# oresat-c3-v1.net
KiCad netlist of a schematic drawn in EAGLE
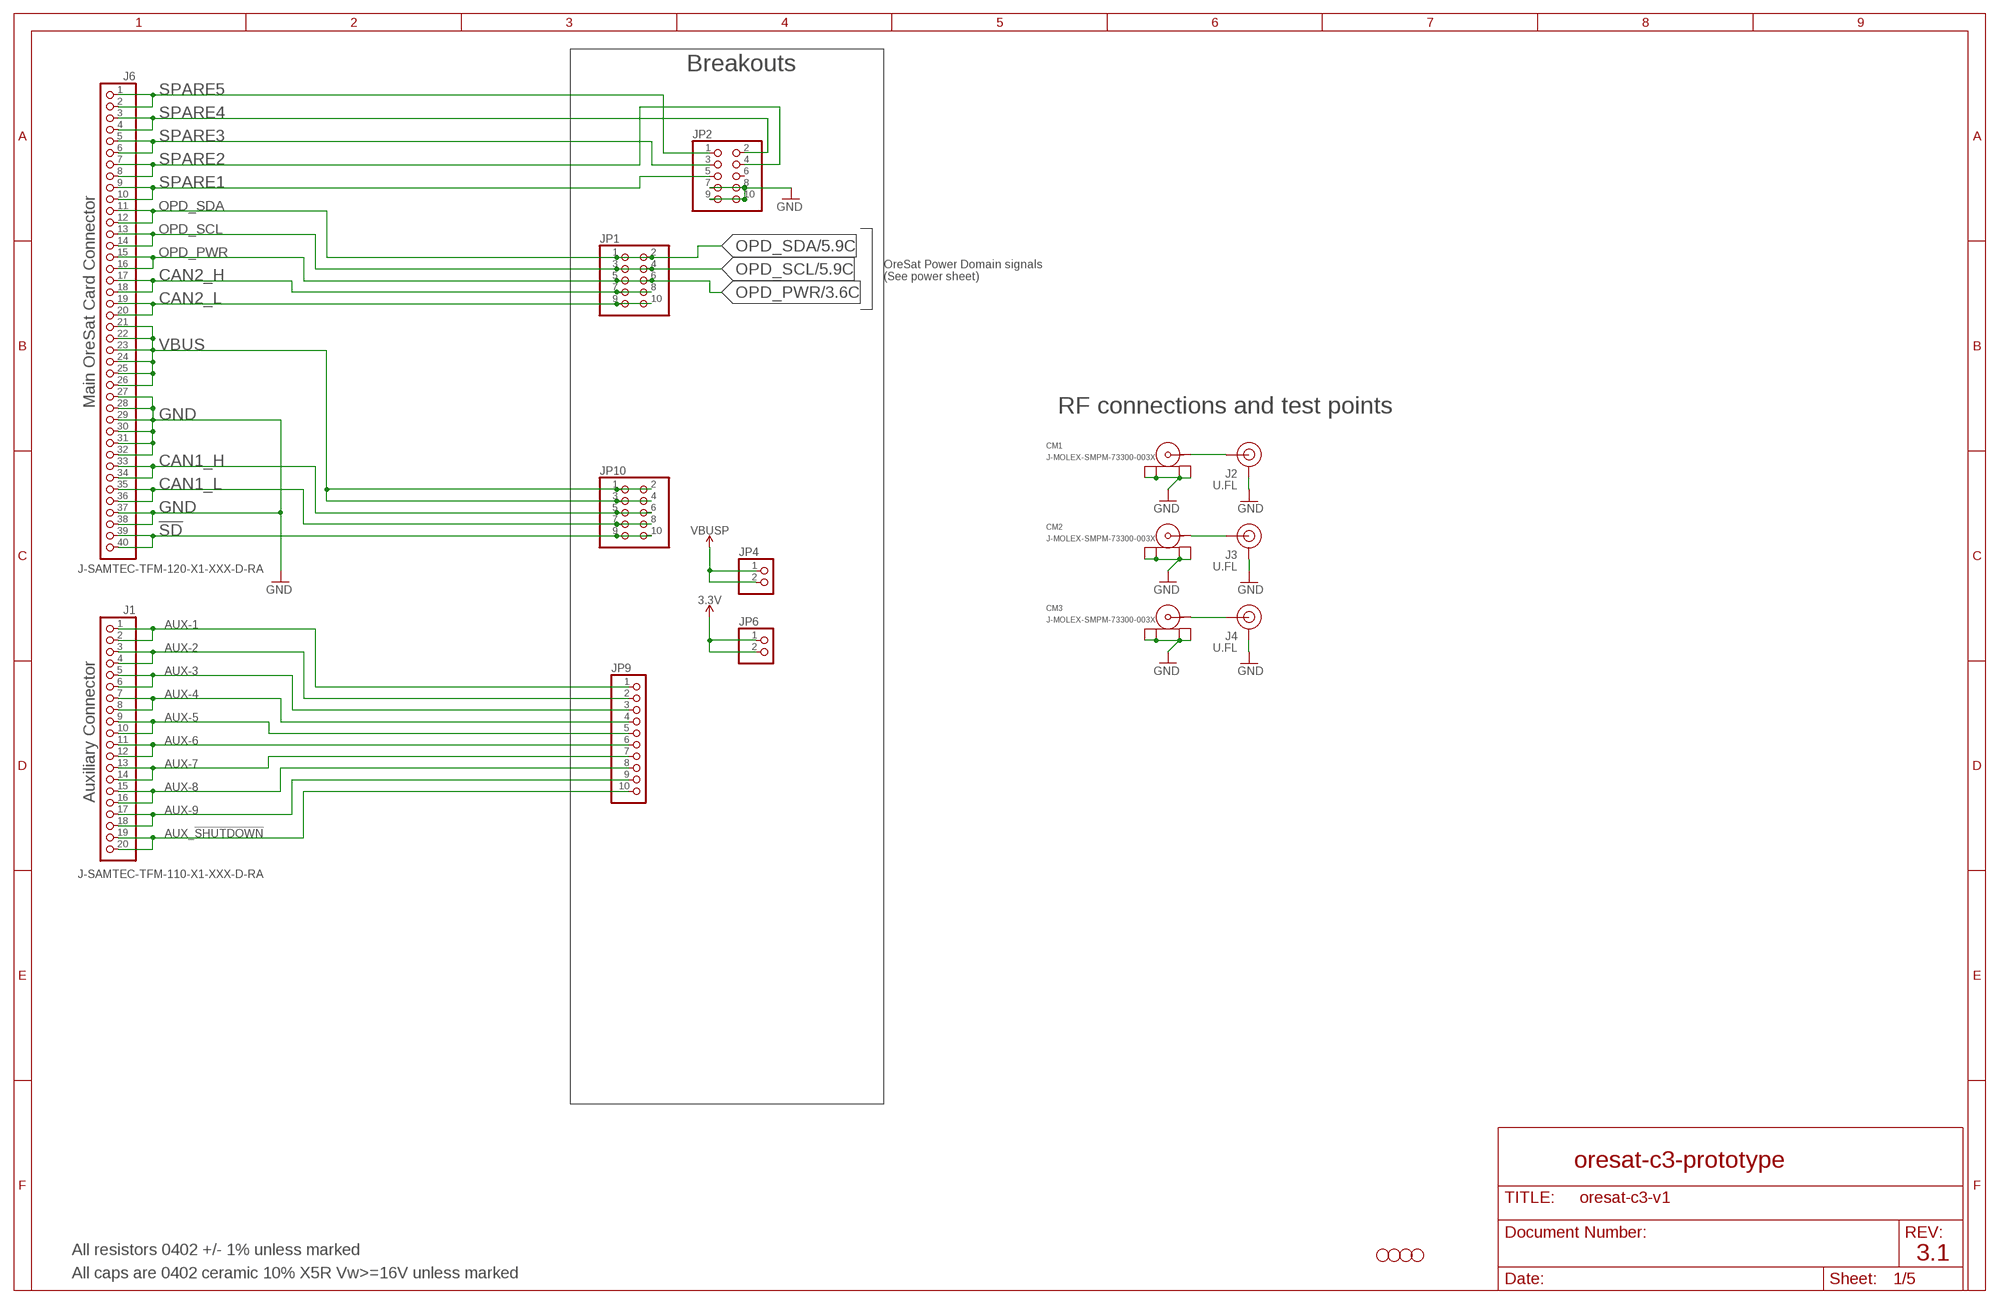
[diagram p0: schematic, sheet 1]
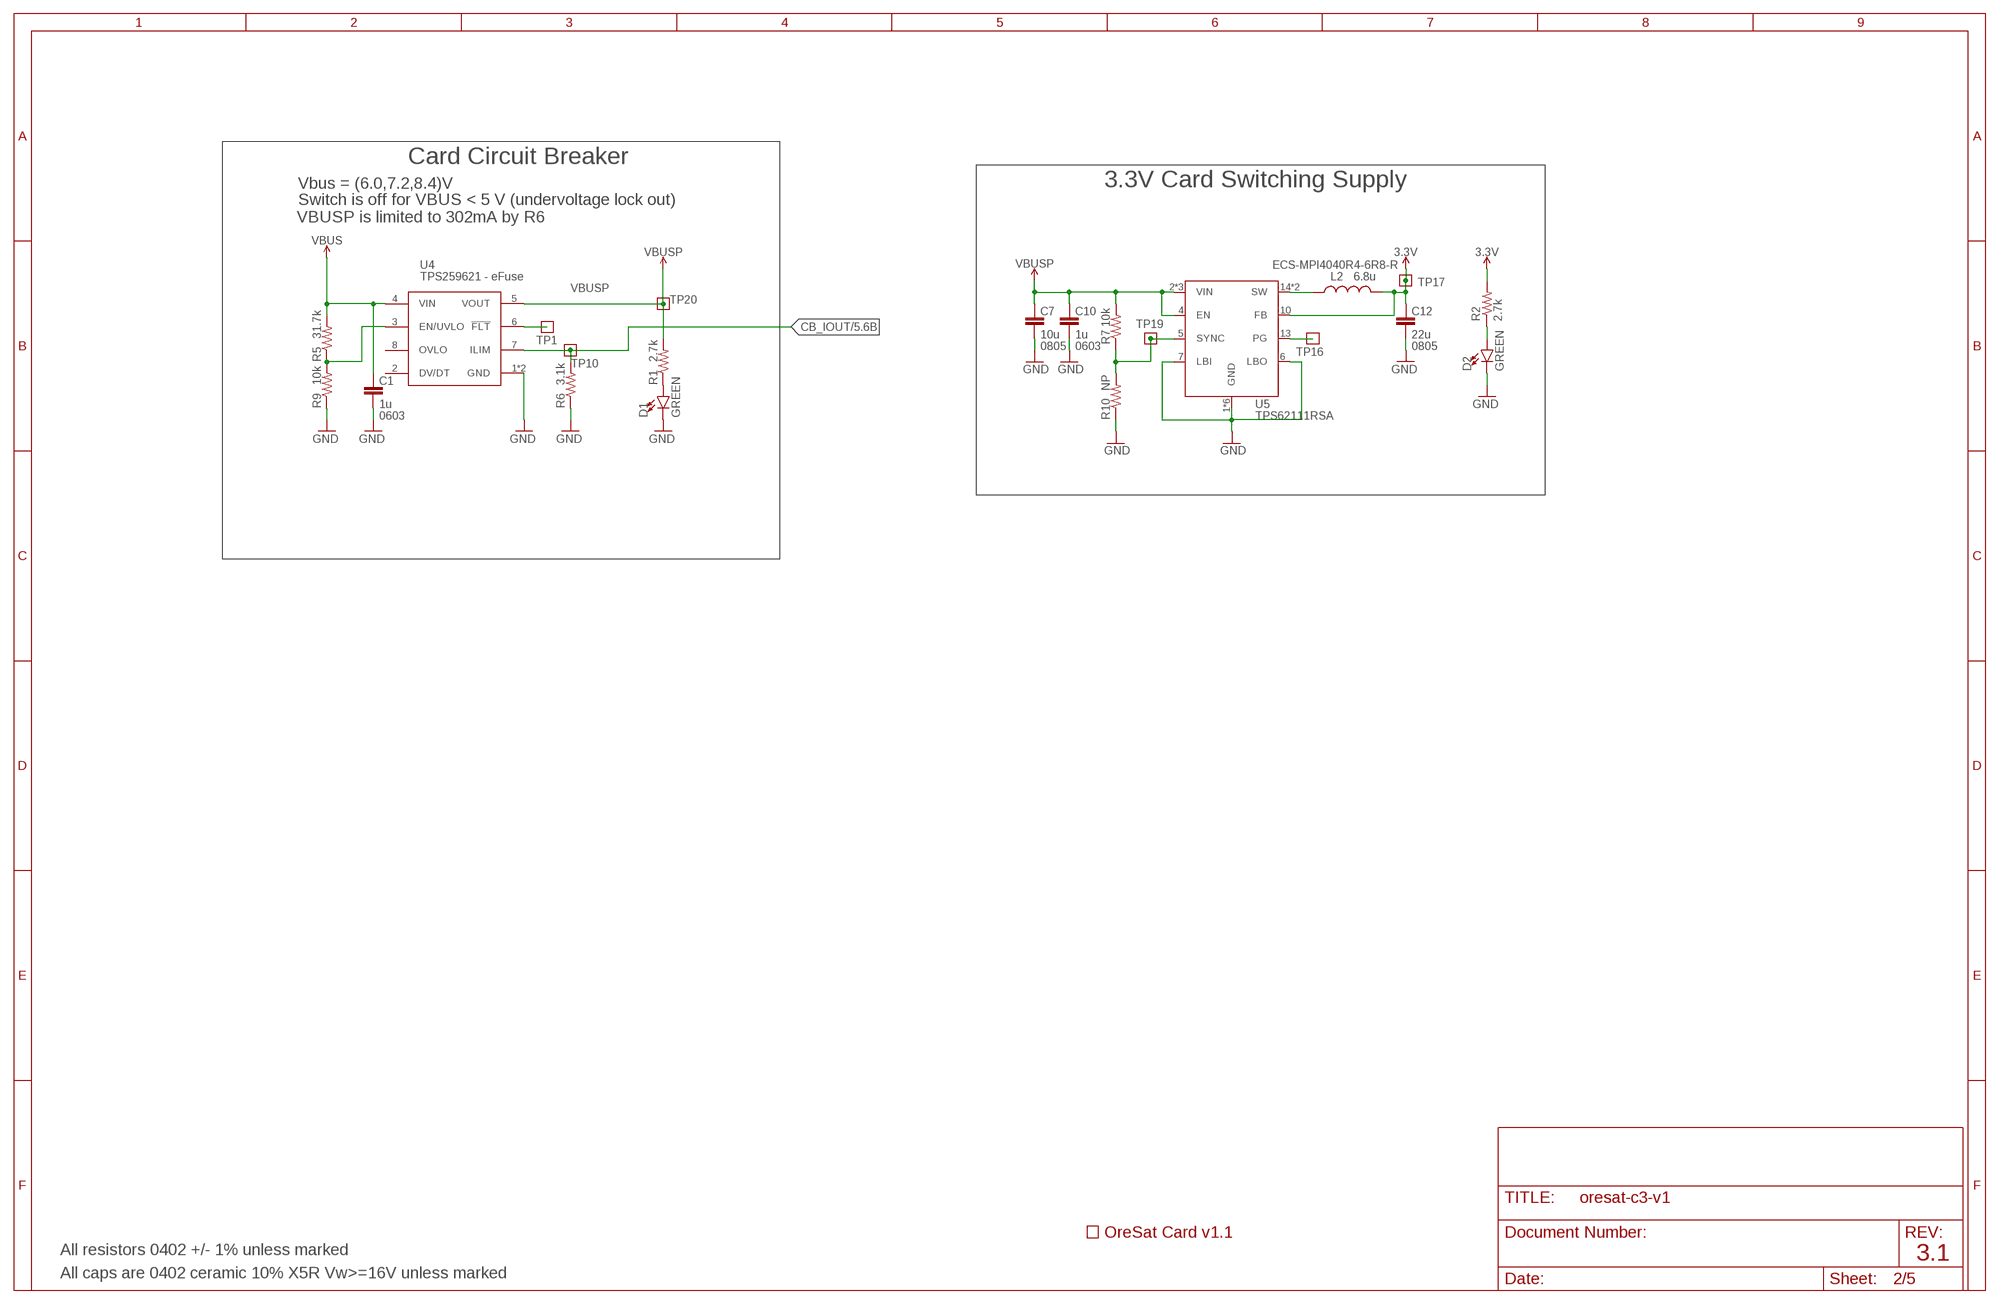
[diagram p1: schematic, sheet 2]
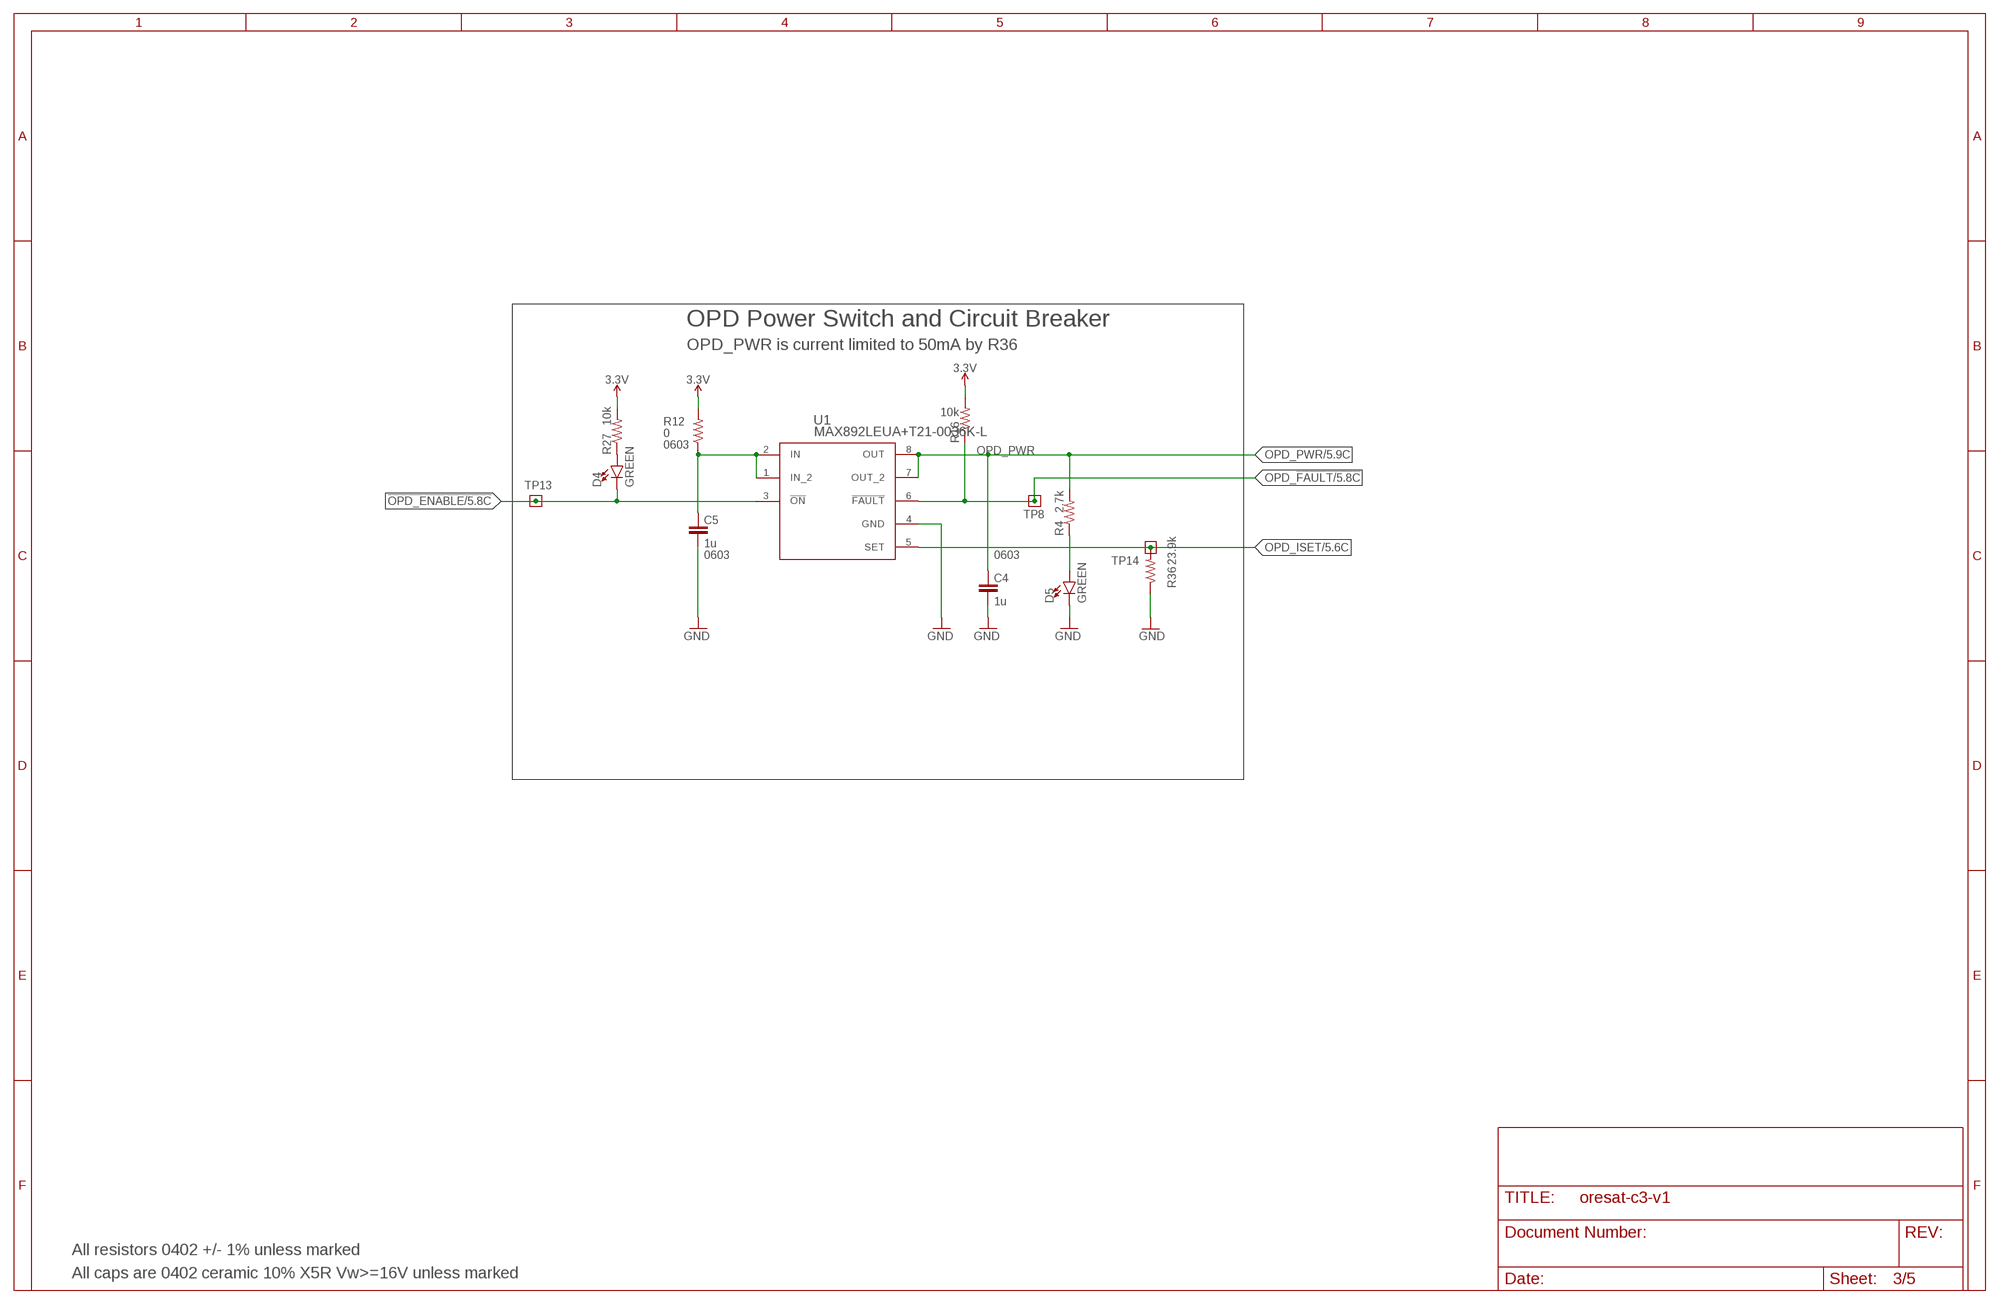
[diagram p2: schematic, sheet 3]
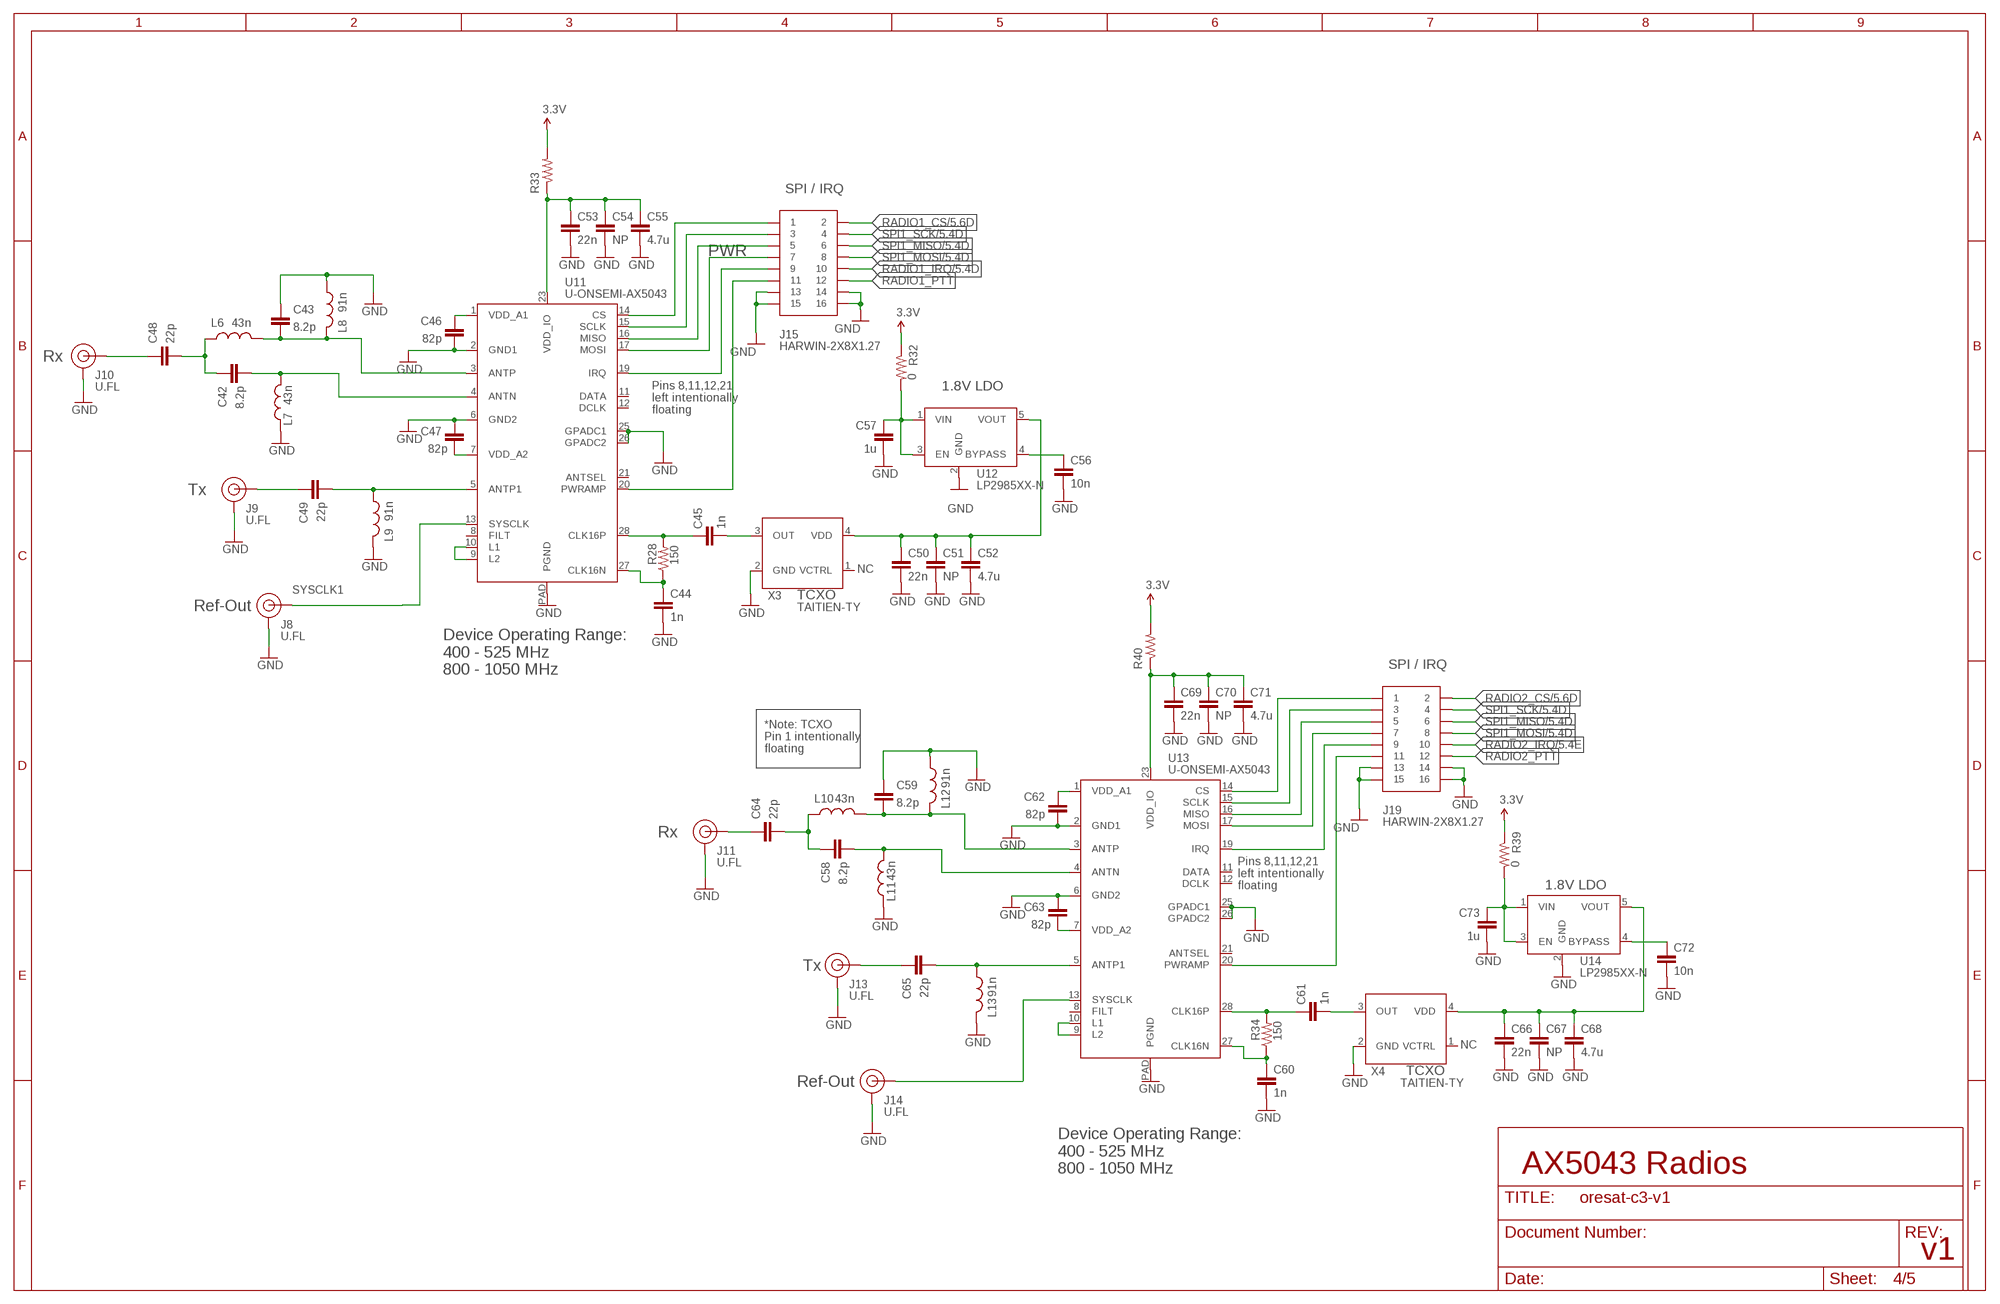
[diagram p3: schematic, sheet 4]
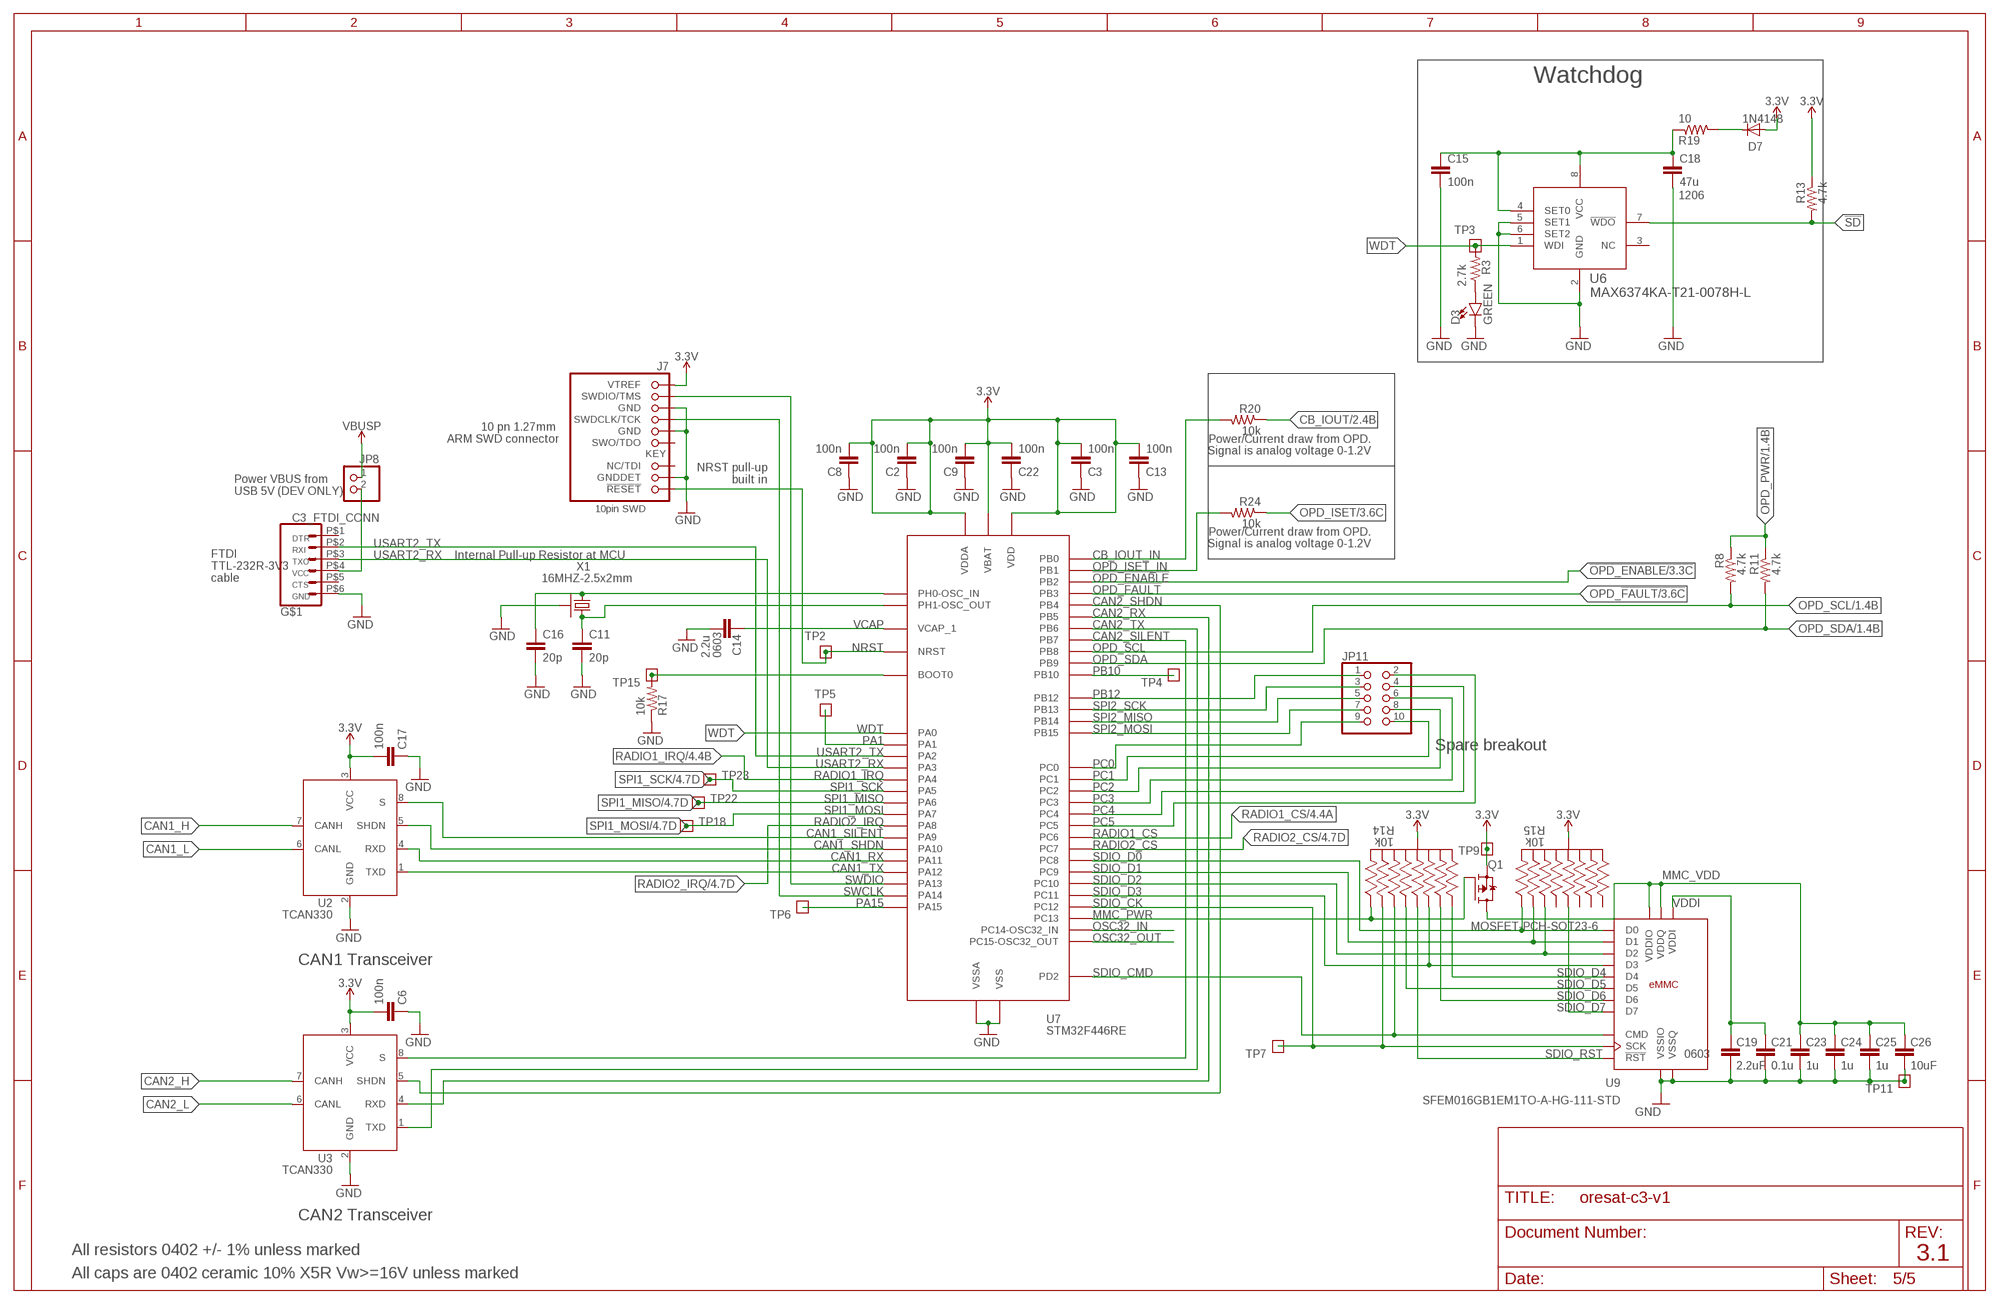
[diagram p4: schematic, sheet 5]

(export (version "E")
  (design (tool "Eeschema 10.0.6"))
  (components
    (comp (ref "C42")
      (value "8.2p")
      (footprint "eagle-import:.0402-C-NOSILK")
      (libsource (lib "eagle-import") (part "C-EU0402-C-NOSILK"))
    )
    (comp (ref "C43")
      (value "8.2p")
      (footprint "eagle-import:.0402-C-NOSILK")
      (libsource (lib "eagle-import") (part "C-EU0402-C-NOSILK"))
    )
    (comp (ref "C44")
      (value "1n")
      (footprint "eagle-import:.0402-C-NOSILK")
      (libsource (lib "eagle-import") (part "C-EU0402-C-NOSILK"))
    )
    (comp (ref "C45")
      (value "1n")
      (footprint "eagle-import:.0402-C-NOSILK")
      (libsource (lib "eagle-import") (part "C-EU0402-C-NOSILK"))
    )
    (comp (ref "C46")
      (value "82p")
      (footprint "eagle-import:.0402-C-NOSILK")
      (libsource (lib "eagle-import") (part "C-EU0402-C-NOSILK"))
    )
    (comp (ref "C47")
      (value "82p")
      (footprint "eagle-import:.0402-C-NOSILK")
      (libsource (lib "eagle-import") (part "C-EU0402-C-NOSILK"))
    )
    (comp (ref "C48")
      (value "22p")
      (footprint "eagle-import:.0402-C-NOSILK")
      (libsource (lib "eagle-import") (part "C-EU0402-C-NOSILK"))
    )
    (comp (ref "C49")
      (value "22p")
      (footprint "eagle-import:.0402-C-NOSILK")
      (libsource (lib "eagle-import") (part "C-EU0402-C-NOSILK"))
    )
    (comp (ref "C50")
      (value "22n")
      (footprint "eagle-import:.0603-C-NOSILK")
      (libsource (lib "eagle-import") (part "C-EU0603-C-NOSILK"))
    )
    (comp (ref "C51")
      (value "NP")
      (footprint "eagle-import:.0603-C-NOSILK")
      (libsource (lib "eagle-import") (part "C-EU0603-C-NOSILK"))
    )
    (comp (ref "C52")
      (value "4.7u")
      (footprint "eagle-import:.0603-C-NOSILK")
      (libsource (lib "eagle-import") (part "C-EU0603-C-NOSILK"))
    )
    (comp (ref "C53")
      (value "22n")
      (footprint "eagle-import:.0603-C-NOSILK")
      (libsource (lib "eagle-import") (part "C-EU0603-C-NOSILK"))
    )
    (comp (ref "C54")
      (value "NP")
      (footprint "eagle-import:.0603-C-NOSILK")
      (libsource (lib "eagle-import") (part "C-EU0603-C-NOSILK"))
    )
    (comp (ref "C55")
      (value "4.7u")
      (footprint "eagle-import:.0603-C-NOSILK")
      (libsource (lib "eagle-import") (part "C-EU0603-C-NOSILK"))
    )
    (comp (ref "C56")
      (value "10n")
      (footprint "eagle-import:.0603-C-NOSILK")
      (libsource (lib "eagle-import") (part "C-EU0603-C-NOSILK"))
    )
    (comp (ref "C57")
      (value "1u")
      (footprint "eagle-import:.0603-C-NOSILK")
      (libsource (lib "eagle-import") (part "C-EU0603-C-NOSILK"))
    )
    (comp (ref "C58")
      (value "8.2p")
      (footprint "eagle-import:.0402-C-NOSILK")
      (libsource (lib "eagle-import") (part "C-EU0402-C-NOSILK"))
    )
    (comp (ref "C59")
      (value "8.2p")
      (footprint "eagle-import:.0402-C-NOSILK")
      (libsource (lib "eagle-import") (part "C-EU0402-C-NOSILK"))
    )
    (comp (ref "C60")
      (value "1n")
      (footprint "eagle-import:.0402-C-NOSILK")
      (libsource (lib "eagle-import") (part "C-EU0402-C-NOSILK"))
    )
    (comp (ref "C61")
      (value "1n")
      (footprint "eagle-import:.0402-C-NOSILK")
      (libsource (lib "eagle-import") (part "C-EU0402-C-NOSILK"))
    )
    (comp (ref "C62")
      (value "82p")
      (footprint "eagle-import:.0402-C-NOSILK")
      (libsource (lib "eagle-import") (part "C-EU0402-C-NOSILK"))
    )
    (comp (ref "C63")
      (value "82p")
      (footprint "eagle-import:.0402-C-NOSILK")
      (libsource (lib "eagle-import") (part "C-EU0402-C-NOSILK"))
    )
    (comp (ref "C64")
      (value "22p")
      (footprint "eagle-import:.0402-C-NOSILK")
      (libsource (lib "eagle-import") (part "C-EU0402-C-NOSILK"))
    )
    (comp (ref "C65")
      (value "22p")
      (footprint "eagle-import:.0402-C-NOSILK")
      (libsource (lib "eagle-import") (part "C-EU0402-C-NOSILK"))
    )
    (comp (ref "C66")
      (value "22n")
      (footprint "eagle-import:.0603-C-NOSILK")
      (libsource (lib "eagle-import") (part "C-EU0603-C-NOSILK"))
    )
    (comp (ref "C67")
      (value "NP")
      (footprint "eagle-import:.0603-C-NOSILK")
      (libsource (lib "eagle-import") (part "C-EU0603-C-NOSILK"))
    )
    (comp (ref "C68")
      (value "4.7u")
      (footprint "eagle-import:.0603-C-NOSILK")
      (libsource (lib "eagle-import") (part "C-EU0603-C-NOSILK"))
    )
    (comp (ref "C69")
      (value "22n")
      (footprint "eagle-import:.0603-C-NOSILK")
      (libsource (lib "eagle-import") (part "C-EU0603-C-NOSILK"))
    )
    (comp (ref "C70")
      (value "NP")
      (footprint "eagle-import:.0603-C-NOSILK")
      (libsource (lib "eagle-import") (part "C-EU0603-C-NOSILK"))
    )
    (comp (ref "C71")
      (value "4.7u")
      (footprint "eagle-import:.0603-C-NOSILK")
      (libsource (lib "eagle-import") (part "C-EU0603-C-NOSILK"))
    )
    (comp (ref "C72")
      (value "10n")
      (footprint "eagle-import:.0603-C-NOSILK")
      (libsource (lib "eagle-import") (part "C-EU0603-C-NOSILK"))
    )
    (comp (ref "C73")
      (value "1u")
      (footprint "eagle-import:.0603-C-NOSILK")
      (libsource (lib "eagle-import") (part "C-EU0603-C-NOSILK"))
    )
    (comp (ref "J8")
      (value "U.FL")
      (footprint "eagle-import:U.FL")
      (libsource (lib "eagle-import") (part "U.FL2PIN"))
    )
    (comp (ref "J9")
      (value "U.FL")
      (footprint "eagle-import:U.FL")
      (libsource (lib "eagle-import") (part "U.FL2PIN"))
    )
    (comp (ref "J10")
      (value "U.FL")
      (footprint "eagle-import:U.FL")
      (libsource (lib "eagle-import") (part "U.FL2PIN"))
    )
    (comp (ref "J11")
      (value "U.FL")
      (footprint "eagle-import:U.FL")
      (libsource (lib "eagle-import") (part "U.FL2PIN"))
    )
    (comp (ref "J13")
      (value "U.FL")
      (footprint "eagle-import:U.FL")
      (libsource (lib "eagle-import") (part "U.FL2PIN"))
    )
    (comp (ref "J14")
      (value "U.FL")
      (footprint "eagle-import:U.FL")
      (libsource (lib "eagle-import") (part "U.FL2PIN"))
    )
    (comp (ref "J15")
      (value "HARWIN-2X8X1.27")
      (footprint "eagle-import:2X8X1.27")
      (libsource (lib "eagle-import") (part "HARWIN-2X8X1.27"))
    )
    (comp (ref "J19")
      (value "HARWIN-2X8X1.27")
      (footprint "eagle-import:2X8X1.27")
      (libsource (lib "eagle-import") (part "HARWIN-2X8X1.27"))
    )
    (comp (ref "L6")
      (value "43n")
      (footprint "eagle-import:.0402-C-NOSILK")
      (libsource (lib "eagle-import") (part "L-US0402-C-NOSILK"))
    )
    (comp (ref "L7")
      (value "43n")
      (footprint "eagle-import:.0402-C-NOSILK")
      (libsource (lib "eagle-import") (part "L-US0402-C-NOSILK"))
    )
    (comp (ref "L8")
      (value "91n")
      (footprint "eagle-import:.0603-C-NOSILK")
      (libsource (lib "eagle-import") (part "L-US0603-C-NOSILK"))
    )
    (comp (ref "L9")
      (value "91n")
      (footprint "eagle-import:.0603-C-NOSILK")
      (libsource (lib "eagle-import") (part "L-US0603-C-NOSILK"))
    )
    (comp (ref "L10")
      (value "43n")
      (footprint "eagle-import:.0402-C-NOSILK")
      (libsource (lib "eagle-import") (part "L-US0402-C-NOSILK"))
    )
    (comp (ref "L11")
      (value "43n")
      (footprint "eagle-import:.0402-C-NOSILK")
      (libsource (lib "eagle-import") (part "L-US0402-C-NOSILK"))
    )
    (comp (ref "L12")
      (value "91n")
      (footprint "eagle-import:.0603-C-NOSILK")
      (libsource (lib "eagle-import") (part "L-US0603-C-NOSILK"))
    )
    (comp (ref "L13")
      (value "91n")
      (footprint "eagle-import:.0603-C-NOSILK")
      (libsource (lib "eagle-import") (part "L-US0603-C-NOSILK"))
    )
    (comp (ref "R28")
      (value "150")
      (footprint "eagle-import:.0402-C-NOSILK")
      (libsource (lib "eagle-import") (part "R-US_0402-C-NOSILK"))
    )
    (comp (ref "R32")
      (value "0")
      (footprint "eagle-import:.0603-C-NOSILK")
      (libsource (lib "eagle-import") (part "R-US_0603-C-NOSILK"))
    )
    (comp (ref "R33")
      (value "0")
      (footprint "eagle-import:.0603-C-NOSILK")
      (libsource (lib "eagle-import") (part "R-US_0603-C-NOSILK"))
    )
    (comp (ref "R34")
      (value "150")
      (footprint "eagle-import:.0402-C-NOSILK")
      (libsource (lib "eagle-import") (part "R-US_0402-C-NOSILK"))
    )
    (comp (ref "R39")
      (value "0")
      (footprint "eagle-import:.0603-C-NOSILK")
      (libsource (lib "eagle-import") (part "R-US_0603-C-NOSILK"))
    )
    (comp (ref "R40")
      (value "0")
      (footprint "eagle-import:.0603-C-NOSILK")
      (libsource (lib "eagle-import") (part "R-US_0603-C-NOSILK"))
    )
    (comp (ref "U11")
      (value "U-ONSEMI-AX5043")
      (footprint "eagle-import:QFN28-5X5-WITH-CENTER-PAD")
      (libsource (lib "eagle-import") (part "U-ONSEMI-AX5043"))
    )
    (comp (ref "U12")
      (value "LP2985XX-N")
      (footprint "eagle-import:SOT-23")
      (libsource (lib "eagle-import") (part "LP2985XX-N"))
    )
    (comp (ref "U13")
      (value "U-ONSEMI-AX5043")
      (footprint "eagle-import:QFN28-5X5-WITH-CENTER-PAD")
      (libsource (lib "eagle-import") (part "U-ONSEMI-AX5043"))
    )
    (comp (ref "U14")
      (value "LP2985XX-N")
      (footprint "eagle-import:SOT-23")
      (libsource (lib "eagle-import") (part "LP2985XX-N"))
    )
    (comp (ref "X3")
      (value "TAITIEN-TY")
      (footprint "eagle-import:2.5X2.0")
      (libsource (lib "eagle-import") (part "TAITIEN-TY"))
    )
    (comp (ref "X4")
      (value "TAITIEN-TY")
      (footprint "eagle-import:2.5X2.0")
      (libsource (lib "eagle-import") (part "TAITIEN-TY"))
    )
    (comp (ref "CM1")
      (value "J-MOLEX-SMPM-73300-003X")
      (footprint "eagle-import:J-MOLEX-SMPM-073300-003X")
      (fields (field (name "MFR") "Molex") (field (name "MPN") "73300-0020"))
      (libsource (lib "eagle-import") (part "J-MOLEX-SMPM-73300-003X"))
    )
    (comp (ref "CM2")
      (value "J-MOLEX-SMPM-73300-003X")
      (footprint "eagle-import:J-MOLEX-SMPM-073300-003X")
      (fields (field (name "MFR") "Molex") (field (name "MPN") "73300-0020"))
      (libsource (lib "eagle-import") (part "J-MOLEX-SMPM-73300-003X"))
    )
    (comp (ref "CM3")
      (value "J-MOLEX-SMPM-73300-003X")
      (footprint "eagle-import:J-MOLEX-SMPM-073300-003X")
      (fields (field (name "MFR") "Molex") (field (name "MPN") "73300-0020"))
      (libsource (lib "eagle-import") (part "J-MOLEX-SMPM-73300-003X"))
    )
    (comp (ref "H1")
      (value "STAND-OFFTIGHT")
      (footprint "eagle-import:STAND-OFF-TIGHT")
      (libsource (lib "eagle-import") (part "STAND-OFFTIGHT"))
    )
    (comp (ref "H2")
      (value "STAND-OFFTIGHT")
      (footprint "eagle-import:STAND-OFF-TIGHT")
      (libsource (lib "eagle-import") (part "STAND-OFFTIGHT"))
    )
    (comp (ref "H3")
      (value "STAND-OFFTIGHT")
      (footprint "eagle-import:STAND-OFF-TIGHT")
      (libsource (lib "eagle-import") (part "STAND-OFFTIGHT"))
    )
    (comp (ref "H4")
      (value "STAND-OFFTIGHT")
      (footprint "eagle-import:STAND-OFF-TIGHT")
      (libsource (lib "eagle-import") (part "STAND-OFFTIGHT"))
    )
    (comp (ref "J1")
      (value "J-SAMTEC-TFM-110-X1-XXX-D-RA")
      (footprint "eagle-import:J-SAMTEC-TFM-110-X1-XXX-D-RA")
      (fields (field (name "MFR") "Samtec") (field (name "MPN") "TFM-110-01-L-D-RA "))
      (libsource (lib "eagle-import") (part "J-SAMTEC-TFM-110-X1-XXX-D-RA"))
    )
    (comp (ref "J2")
      (value "U.FL")
      (footprint "eagle-import:U.FL")
      (libsource (lib "eagle-import") (part "U.FL2PIN"))
    )
    (comp (ref "J3")
      (value "U.FL")
      (footprint "eagle-import:U.FL")
      (libsource (lib "eagle-import") (part "U.FL2PIN"))
    )
    (comp (ref "J4")
      (value "U.FL")
      (footprint "eagle-import:U.FL")
      (libsource (lib "eagle-import") (part "U.FL2PIN"))
    )
    (comp (ref "J6")
      (value "J-SAMTEC-TFM-120-X1-XXX-D-RA")
      (footprint "eagle-import:J-SAMTEC-TFM-120-X1-XXX-D-RA")
      (fields (field (name "MFR") "Samtec") (field (name "MPN") "TFM-120-01-L-D-RA"))
      (libsource (lib "eagle-import") (part "J-SAMTEC-TFM-120-X1-XXX-D-RA"))
    )
    (comp (ref "JP1")
      (value "PINHD-2X5")
      (footprint "eagle-import:2X05")
      (libsource (lib "eagle-import") (part "PINHD-2X5"))
    )
    (comp (ref "JP2")
      (value "PINHD-2X5")
      (footprint "eagle-import:2X05")
      (libsource (lib "eagle-import") (part "PINHD-2X5"))
    )
    (comp (ref "JP4")
      (value "PINHD-1X2")
      (footprint "eagle-import:1X02")
      (libsource (lib "eagle-import") (part "PINHD-1X2"))
    )
    (comp (ref "JP6")
      (value "PINHD-1X2")
      (footprint "eagle-import:1X02")
      (libsource (lib "eagle-import") (part "PINHD-1X2"))
    )
    (comp (ref "JP9")
      (value "PINHD-1X10")
      (footprint "eagle-import:1X10")
      (libsource (lib "eagle-import") (part "PINHD-1X10"))
    )
    (comp (ref "JP10")
      (value "PINHD-2X5")
      (footprint "eagle-import:2X05")
      (libsource (lib "eagle-import") (part "PINHD-2X5"))
    )
    (comp (ref "C1")
      (value "1u")
      (footprint "eagle-import:.0603-B-NOSILK")
      (fields (field (name "MFR") "Samsung") (field (name "MPN") "CL05B104KO5NNNC"))
      (libsource (lib "eagle-import") (part "C-EU0603-B-NOSILK"))
    )
    (comp (ref "C7")
      (value "10u")
      (footprint "eagle-import:.0805-B-NOSILK")
      (libsource (lib "eagle-import") (part "C-EU0805-B-NOSILK"))
    )
    (comp (ref "C10")
      (value "1u")
      (footprint "eagle-import:.0603-B-NOSILK")
      (fields (field (name "MFR") "Samsung") (field (name "MPN") "CL05B104KO5NNNC"))
      (libsource (lib "eagle-import") (part "C-EU0603-B-NOSILK"))
    )
    (comp (ref "C12")
      (value "22u")
      (footprint "eagle-import:.0805-B-NOSILK")
      (libsource (lib "eagle-import") (part "C-EU0805-B-NOSILK"))
    )
    (comp (ref "D1")
      (value "GREEN")
      (footprint "eagle-import:LED-0603")
      (libsource (lib "eagle-import") (part "LED-GREEN0603"))
    )
    (comp (ref "D2")
      (value "GREEN")
      (footprint "eagle-import:LED-0603")
      (libsource (lib "eagle-import") (part "LED-GREEN0603"))
    )
    (comp (ref "L2")
      (value "6.8u")
      (footprint "eagle-import:ECS-MPI4040")
      (fields (field (name "MFR") "ECS") (field (name "MPN") "ECS-MPI4040R4-6R8-R"))
      (libsource (lib "eagle-import") (part "L-ECS-MPI4040"))
    )
    (comp (ref "R1")
      (value "2.7k")
      (footprint "eagle-import:.0402-B-NOSILK")
      (fields (field (name "MFR") "Samsung") (field (name "MPN") "RC1005F6653CS"))
      (libsource (lib "eagle-import") (part "R-US_0402-B-NOSILK"))
    )
    (comp (ref "R2")
      (value "2.7k")
      (footprint "eagle-import:.0402-B-NOSILK")
      (fields (field (name "MFR") "Samsung") (field (name "MPN") "RC1005F6653CS"))
      (libsource (lib "eagle-import") (part "R-US_0402-B-NOSILK"))
    )
    (comp (ref "R5")
      (value "31.7k")
      (footprint "eagle-import:.0402-B-NOSILK")
      (fields (field (name "MFR") "Samsung") (field (name "MPN") "RC1005F6653CS"))
      (libsource (lib "eagle-import") (part "R-US_0402-B-NOSILK"))
    )
    (comp (ref "R6")
      (value "3.1k")
      (footprint "eagle-import:.0402-B-NOSILK")
      (fields (field (name "MFR") "Samsung") (field (name "MPN") "RC1005F6653CS"))
      (libsource (lib "eagle-import") (part "R-US_0402-B-NOSILK"))
    )
    (comp (ref "R7")
      (value "10k")
      (footprint "eagle-import:.0402-B-NOSILK")
      (fields (field (name "MFR") "Samsung") (field (name "MPN") "RC1005F6653CS"))
      (libsource (lib "eagle-import") (part "R-US_0402-B-NOSILK"))
    )
    (comp (ref "R9")
      (value "10k")
      (footprint "eagle-import:.0402-B-NOSILK")
      (fields (field (name "MFR") "Samsung") (field (name "MPN") "RC1005F6653CS"))
      (libsource (lib "eagle-import") (part "R-US_0402-B-NOSILK"))
    )
    (comp (ref "R10")
      (value "NP")
      (footprint "eagle-import:.0402-B-NOSILK")
      (fields (field (name "MFR") "Samsung") (field (name "MPN") "RC1005F6653CS"))
      (libsource (lib "eagle-import") (part "R-US_0402-B-NOSILK"))
    )
    (comp (ref "TP1")
      (value "TEST-POINT")
      (footprint "eagle-import:2MM-TEST-POINT")
      (libsource (lib "eagle-import") (part "TEST-POINT"))
    )
    (comp (ref "TP10")
      (value "TEST-POINT")
      (footprint "eagle-import:2MM-TEST-POINT")
      (libsource (lib "eagle-import") (part "TEST-POINT"))
    )
    (comp (ref "TP16")
      (value "TEST-POINT")
      (footprint "eagle-import:2MM-TEST-POINT")
      (libsource (lib "eagle-import") (part "TEST-POINT"))
    )
    (comp (ref "TP17")
      (value "TEST-POINT")
      (footprint "eagle-import:2MM-TEST-POINT")
      (libsource (lib "eagle-import") (part "TEST-POINT"))
    )
    (comp (ref "TP19")
      (value "TEST-POINT")
      (footprint "eagle-import:2MM-TEST-POINT")
      (libsource (lib "eagle-import") (part "TEST-POINT"))
    )
    (comp (ref "TP20")
      (value "TEST-POINT")
      (footprint "eagle-import:2MM-TEST-POINT")
      (libsource (lib "eagle-import") (part "TEST-POINT"))
    )
    (comp (ref "U$1")
      (value "ORESAT-CARD-V1.1-3XRF")
      (footprint "eagle-import:ORESAT-CARD-V1.1-3XRF")
      (libsource (lib "eagle-import") (part "ORESAT-CARD-V1.1-3XRF"))
    )
    (comp (ref "U4")
      (value "TPS259621 - eFuse")
      (footprint "eagle-import:SO-POWERPAD-8")
      (libsource (lib "eagle-import") (part "TPS2596XX"))
    )
    (comp (ref "U5")
      (value "TPS62111RSA")
      (footprint "eagle-import:S-PVQFN-16")
      (fields (field (name "MFR") "TI"))
      (libsource (lib "eagle-import") (part "TPS6211X"))
    )
    (comp (ref "C4")
      (value "1u")
      (footprint "eagle-import:.0603-B-NOSILK")
      (fields (field (name "MFR") "Samsung") (field (name "MPN") "CL05B104KO5NNNC"))
      (libsource (lib "eagle-import") (part "C-EU0603-B-NOSILK"))
    )
    (comp (ref "C5")
      (value "1u")
      (footprint "eagle-import:.0603-B-NOSILK")
      (fields (field (name "MFR") "Samsung") (field (name "MPN") "CL05B104KO5NNNC"))
      (libsource (lib "eagle-import") (part "C-EU0603-B-NOSILK"))
    )
    (comp (ref "D4")
      (value "GREEN")
      (footprint "eagle-import:LED-0603")
      (libsource (lib "eagle-import") (part "LED-GREEN0603"))
    )
    (comp (ref "D5")
      (value "GREEN")
      (footprint "eagle-import:LED-0603")
      (libsource (lib "eagle-import") (part "LED-GREEN0603"))
    )
    (comp (ref "R4")
      (value "2.7k")
      (footprint "eagle-import:.0402-B-NOSILK")
      (fields (field (name "MFR") "Samsung") (field (name "MPN") "RC1005F6653CS"))
      (libsource (lib "eagle-import") (part "R-US_0402-B-NOSILK"))
    )
    (comp (ref "R12")
      (value "0")
      (footprint "eagle-import:.0603-B-NOSILK")
      (fields (field (name "MFR") "Samsung") (field (name "MPN") "RC1005F6653CS"))
      (libsource (lib "eagle-import") (part "R-US_0603-B-NOSILK"))
    )
    (comp (ref "R16")
      (value "10k")
      (footprint "eagle-import:.0402-B-NOSILK")
      (fields (field (name "MFR") "Samsung") (field (name "MPN") "RC1005F6653CS"))
      (libsource (lib "eagle-import") (part "R-US_0402-B-NOSILK"))
    )
    (comp (ref "R27")
      (value "10k")
      (footprint "eagle-import:.0402-B-NOSILK")
      (fields (field (name "MFR") "Samsung") (field (name "MPN") "RC1005F6653CS"))
      (libsource (lib "eagle-import") (part "R-US_0402-B-NOSILK"))
    )
    (comp (ref "R36")
      (value "23.9k")
      (footprint "eagle-import:.0402-B-NOSILK")
      (fields (field (name "MFR") "Samsung") (field (name "MPN") "RC1005F6653CS"))
      (libsource (lib "eagle-import") (part "R-US_0402-B-NOSILK"))
    )
    (comp (ref "TP8")
      (value "TEST-POINT")
      (footprint "eagle-import:2MM-TEST-POINT")
      (libsource (lib "eagle-import") (part "TEST-POINT"))
    )
    (comp (ref "TP13")
      (value "TEST-POINT")
      (footprint "eagle-import:2MM-TEST-POINT")
      (libsource (lib "eagle-import") (part "TEST-POINT"))
    )
    (comp (ref "TP14")
      (value "TEST-POINT")
      (footprint "eagle-import:2MM-TEST-POINT")
      (libsource (lib "eagle-import") (part "TEST-POINT"))
    )
    (comp (ref "U1")
      (value "MAX892LEUA+T21-0036K-L")
      (footprint "eagle-import:21-0036K-L")
      (fields (field (name "MANUFACTURER_PART_NUMBER") "MAX892LEUA+T"))
      (libsource (lib "eagle-import") (part "MAX892LEUA+T21-0036K-L"))
    )
    (comp (ref "C2")
      (value "100n")
      (footprint "eagle-import:.0402-B-NOSILK")
      (fields (field (name "MFR") "Samsung") (field (name "MPN") "CL05B104KO5NNNC"))
      (libsource (lib "eagle-import") (part "C-EU0402-B-NOSILK"))
    )
    (comp (ref "C3")
      (value "100n")
      (footprint "eagle-import:.0402-B-NOSILK")
      (fields (field (name "MFR") "Samsung") (field (name "MPN") "CL05B104KO5NNNC"))
      (libsource (lib "eagle-import") (part "C-EU0402-B-NOSILK"))
    )
    (comp (ref "C6")
      (value "100n")
      (footprint "eagle-import:.0402-B-NOSILK")
      (fields (field (name "MFR") "Samsung") (field (name "MPN") "CL05B104KO5NNNC"))
      (libsource (lib "eagle-import") (part "C-EU0402-B-NOSILK"))
    )
    (comp (ref "C8")
      (value "100n")
      (footprint "eagle-import:.0402-B-NOSILK")
      (fields (field (name "MFR") "Samsung") (field (name "MPN") "CL05B104KO5NNNC"))
      (libsource (lib "eagle-import") (part "C-EU0402-B-NOSILK"))
    )
    (comp (ref "C9")
      (value "100n")
      (footprint "eagle-import:.0402-B-NOSILK")
      (fields (field (name "MFR") "Samsung") (field (name "MPN") "CL05B104KO5NNNC"))
      (libsource (lib "eagle-import") (part "C-EU0402-B-NOSILK"))
    )
    (comp (ref "C11")
      (value "20p")
      (footprint "eagle-import:.0402-B-NOSILK")
      (fields (field (name "MFR") "Samsung") (field (name "MPN") "CL05C200JB51PNC"))
      (libsource (lib "eagle-import") (part "rcl_custom_C-EU0402-B-NOSILK"))
    )
    (comp (ref "C13")
      (value "100n")
      (footprint "eagle-import:.0402-B-NOSILK")
      (fields (field (name "MFR") "Samsung") (field (name "MPN") "CL05B104KO5NNNC"))
      (libsource (lib "eagle-import") (part "C-EU0402-B-NOSILK"))
    )
    (comp (ref "C14")
      (value "2.2u")
      (footprint "eagle-import:.0603-B-NOSILK")
      (fields (field (name "MFR") "Samsung") (field (name "MPN") "CL05B104KO5NNNC"))
      (libsource (lib "eagle-import") (part "C-EU0603-B-NOSILK"))
    )
    (comp (ref "C15")
      (value "100n")
      (footprint "eagle-import:.0402-B-NOSILK")
      (fields (field (name "MFR") "Samsung") (field (name "MPN") "CL05C200JB51PNC"))
      (libsource (lib "eagle-import") (part "C-EU0402-B-NOSILK"))
    )
    (comp (ref "C16")
      (value "20p")
      (footprint "eagle-import:.0402-B-NOSILK")
      (fields (field (name "MFR") "Samsung") (field (name "MPN") "CL05C200JB51PNC"))
      (libsource (lib "eagle-import") (part "C-EU0402-B-NOSILK"))
    )
    (comp (ref "C17")
      (value "100n")
      (footprint "eagle-import:.0402-B-NOSILK")
      (fields (field (name "MFR") "Samsung") (field (name "MPN") "CL05B104KO5NNNC"))
      (libsource (lib "eagle-import") (part "C-EU0402-B-NOSILK"))
    )
    (comp (ref "C18")
      (value "47u")
      (footprint "eagle-import:1206-B")
      (fields (field (name "MFR") "Samsung") (field (name "MPN") "CL05C200JB51PNC"))
      (libsource (lib "eagle-import") (part "C-EU1206-B"))
    )
    (comp (ref "C19")
      (value "2.2uF")
      (footprint "eagle-import:.0603-B-NOSILK")
      (fields (field (name "MFR") "Samsung") (field (name "MPN") "CL05B104KO5NNNC"))
      (libsource (lib "eagle-import") (part "C-EU0603-B-NOSILK"))
    )
    (comp (ref "C21")
      (value "0.1u")
      (footprint "eagle-import:.0603-B-NOSILK")
      (fields (field (name "MFR") "Samsung") (field (name "MPN") "CL05B104KO5NNNC"))
      (libsource (lib "eagle-import") (part "C-EU0603-B-NOSILK"))
    )
    (comp (ref "C22")
      (value "100n")
      (footprint "eagle-import:.0402-B-NOSILK")
      (fields (field (name "MFR") "Samsung") (field (name "MPN") "CL05B104KO5NNNC"))
      (libsource (lib "eagle-import") (part "C-EU0402-B-NOSILK"))
    )
    (comp (ref "C23")
      (value "1u")
      (footprint "eagle-import:.0603-B-NOSILK")
      (fields (field (name "MFR") "Samsung") (field (name "MPN") "CL05B104KO5NNNC"))
      (libsource (lib "eagle-import") (part "C-EU0603-B-NOSILK"))
    )
    (comp (ref "C24")
      (value "1u")
      (footprint "eagle-import:.0603-B-NOSILK")
      (fields (field (name "MFR") "Samsung") (field (name "MPN") "CL05B104KO5NNNC"))
      (libsource (lib "eagle-import") (part "C-EU0603-B-NOSILK"))
    )
    (comp (ref "C25")
      (value "1u")
      (footprint "eagle-import:.0603-B-NOSILK")
      (fields (field (name "MFR") "Samsung") (field (name "MPN") "CL05B104KO5NNNC"))
      (libsource (lib "eagle-import") (part "C-EU0603-B-NOSILK"))
    )
    (comp (ref "C26")
      (value "10uF")
      (footprint "eagle-import:.0603-B-NOSILK")
      (fields (field (name "MFR") "Samsung") (field (name "MPN") "CL05B104KO5NNNC"))
      (libsource (lib "eagle-import") (part "C-EU0603-B-NOSILK"))
    )
    (comp (ref "D3")
      (value "GREEN")
      (footprint "eagle-import:LED-0603")
      (libsource (lib "eagle-import") (part "LED-GREEN0603"))
    )
    (comp (ref "D7")
      (value "1N4148")
      (footprint "eagle-import:SOD-323")
      (libsource (lib "eagle-import") (part "DIODESOD"))
    )
    (comp (ref "J7")
      (value "FTSH-105-XX-X-DV-K")
      (footprint "eagle-import:CON10_2X5_DUK_FTSH")
      (fields (field (name "MFR") "Samtec") (field (name "MPN") "FTSH-105-01-F-DV-K"))
      (libsource (lib "eagle-import") (part "FTSH-105-XX-X-DV-K"))
    )
    (comp (ref "JP8")
      (value "PINHD-1X2")
      (footprint "eagle-import:1X02")
      (libsource (lib "eagle-import") (part "pinhead_325_PINHD-1X2"))
    )
    (comp (ref "JP11")
      (value "PINHD-2X5")
      (footprint "eagle-import:2X05")
      (libsource (lib "eagle-import") (part "PINHD-2X5"))
    )
    (comp (ref "Q1")
      (value "MOSFET-PCH-SOT23-6")
      (footprint "eagle-import:SOT23-6")
      (libsource (lib "eagle-import") (part "MOSFET-PCH-SOT23-6"))
    )
    (comp (ref "R3")
      (value "2.7k")
      (footprint "eagle-import:.0402-B-NOSILK")
      (fields (field (name "MFR") "Samsung") (field (name "MPN") "RC1005F6653CS"))
      (libsource (lib "eagle-import") (part "R-US_0402-B-NOSILK"))
    )
    (comp (ref "R8")
      (value "4.7k")
      (footprint "eagle-import:.0402-B-NOSILK")
      (libsource (lib "eagle-import") (part "R-US_0402-B-NOSILK"))
    )
    (comp (ref "R11")
      (value "4.7k")
      (footprint "eagle-import:.0402-B-NOSILK")
      (libsource (lib "eagle-import") (part "R-US_0402-B-NOSILK"))
    )
    (comp (ref "R13")
      (value "4.7k")
      (footprint "eagle-import:.0402-B-NOSILK")
      (libsource (lib "eagle-import") (part "R-US_0402-B-NOSILK"))
    )
    (comp (ref "R14")
      (value "10k")
      (footprint "eagle-import:ARRAY_EXBA-M")
      (fields (field (name "MANUFACTURER_PART_NUMBER") "EXBA10P391J"))
      (libsource (lib "eagle-import") (part "EXB-A10P391JC_ARRAY_EXBA-M"))
    )
    (comp (ref "R15")
      (value "10k")
      (footprint "eagle-import:ARRAY_EXBA-M")
      (fields (field (name "MANUFACTURER_PART_NUMBER") "EXBA10P391J"))
      (libsource (lib "eagle-import") (part "EXB-A10P391JC_ARRAY_EXBA-M"))
    )
    (comp (ref "R17")
      (value "10k")
      (footprint "eagle-import:.0402-B-NOSILK")
      (fields (field (name "MFR") "Samsung") (field (name "MPN") "RC1005F6653CS"))
      (libsource (lib "eagle-import") (part "R-US_0402-B-NOSILK"))
    )
    (comp (ref "R19")
      (value "10")
      (footprint "eagle-import:.0402-B-NOSILK")
      (libsource (lib "eagle-import") (part "R-US_0402-B-NOSILK"))
    )
    (comp (ref "R20")
      (value "10k")
      (footprint "eagle-import:.0402-B-NOSILK")
      (libsource (lib "eagle-import") (part "R-US_0402-B-NOSILK"))
    )
    (comp (ref "R24")
      (value "10k")
      (footprint "eagle-import:.0402-B-NOSILK")
      (libsource (lib "eagle-import") (part "R-US_0402-B-NOSILK"))
    )
    (comp (ref "TP2")
      (value "TEST-POINT")
      (footprint "eagle-import:2MM-TEST-POINT")
      (libsource (lib "eagle-import") (part "TEST-POINT"))
    )
    (comp (ref "TP3")
      (value "TEST-POINT")
      (footprint "eagle-import:2MM-TEST-POINT")
      (libsource (lib "eagle-import") (part "TEST-POINT"))
    )
    (comp (ref "TP4")
      (value "TEST-POINT")
      (footprint "eagle-import:2MM-TEST-POINT")
      (libsource (lib "eagle-import") (part "TEST-POINT"))
    )
    (comp (ref "TP5")
      (value "TEST-POINT")
      (footprint "eagle-import:2MM-TEST-POINT")
      (libsource (lib "eagle-import") (part "TEST-POINT"))
    )
    (comp (ref "TP6")
      (value "TEST-POINT")
      (footprint "eagle-import:2MM-TEST-POINT")
      (libsource (lib "eagle-import") (part "TEST-POINT"))
    )
    (comp (ref "TP7")
      (value "TEST-POINT")
      (footprint "eagle-import:2MM-TEST-POINT")
      (libsource (lib "eagle-import") (part "TEST-POINT"))
    )
    (comp (ref "TP9")
      (value "TEST-POINT")
      (footprint "eagle-import:2MM-TEST-POINT")
      (libsource (lib "eagle-import") (part "TEST-POINT"))
    )
    (comp (ref "TP11")
      (value "TEST-POINT")
      (footprint "eagle-import:2MM-TEST-POINT")
      (libsource (lib "eagle-import") (part "TEST-POINT"))
    )
    (comp (ref "TP15")
      (value "TEST-POINT")
      (footprint "eagle-import:2MM-TEST-POINT")
      (libsource (lib "eagle-import") (part "TEST-POINT"))
    )
    (comp (ref "TP18")
      (value "TEST-POINT")
      (footprint "eagle-import:2MM-TEST-POINT")
      (libsource (lib "eagle-import") (part "TEST-POINT"))
    )
    (comp (ref "TP22")
      (value "TEST-POINT")
      (footprint "eagle-import:2MM-TEST-POINT")
      (libsource (lib "eagle-import") (part "TEST-POINT"))
    )
    (comp (ref "TP23")
      (value "TEST-POINT")
      (footprint "eagle-import:2MM-TEST-POINT")
      (libsource (lib "eagle-import") (part "TEST-POINT"))
    )
    (comp (ref "U$2")
      (value "C3_FTDI_CONN")
      (footprint "eagle-import:6_PIN_SERIAL_TARGET_SIDE_W_SILK")
      (libsource (lib "eagle-import") (part "C3_FTDI_CONN"))
    )
    (comp (ref "U2")
      (value "TCAN330")
      (footprint "eagle-import:SOT23-8_TI-DCN")
      (fields (field (name "MFR") "Texas Instruments") (field (name "MPN") "TCAN330GDCNT"))
      (libsource (lib "eagle-import") (part "TCAN330"))
    )
    (comp (ref "U3")
      (value "TCAN330")
      (footprint "eagle-import:SOT23-8_TI-DCN")
      (fields (field (name "MFR") "Texas Instruments") (field (name "MPN") "TCAN330GDCNT"))
      (libsource (lib "eagle-import") (part "TCAN330"))
    )
    (comp (ref "U6")
      (value "MAX6374KA-T21-0078H-L")
      (footprint "eagle-import:21-0078H-L")
      (fields (field (name "MANUFACTURER_PART_NUMBER") "max6374kat"))
      (libsource (lib "eagle-import") (part "MAX6374KA-T21-0078H-L"))
    )
    (comp (ref "U7")
      (value "STM32F446RE")
      (footprint "eagle-import:QFP-10X10-64")
      (libsource (lib "eagle-import") (part "STM32F446RE"))
    )
    (comp (ref "U9")
      (value "SFEM016GB1EM1TO-A-HG-111-STD")
      (footprint "eagle-import:BGA-153(11.5X13)(EMMC-BA)")
      (libsource (lib "eagle-import") (part "EMMC+RESET-BA"))
    )
    (comp (ref "X1")
      (value "16MHZ-2.5x2mm")
      (footprint "eagle-import:CRYSTAL_2.5X2")
      (fields (field (name "MFR") "ECS Inc.") (field (name "MPN") "ECS-160-10-36Q-ES-TR"))
      (libsource (lib "eagle-import") (part "CRYSTAL-WITH-GND"))
    )
  )
  (nets
    (net (code "1") (name "3.3V") (class "Default")
      (node (ref "C12") (pin "1") (pinfunction "1_1") (pintype "passive"))
      (node (ref "C13") (pin "2") (pinfunction "2_2") (pintype "passive"))
      (node (ref "C17") (pin "2") (pinfunction "2_2") (pintype "passive"))
      (node (ref "C2") (pin "2") (pinfunction "2_2") (pintype "passive"))
      (node (ref "C22") (pin "2") (pinfunction "2_2") (pintype "passive"))
      (node (ref "C3") (pin "2") (pinfunction "2_2") (pintype "passive"))
      (node (ref "C6") (pin "2") (pinfunction "2_2") (pintype "passive"))
      (node (ref "C8") (pin "2") (pinfunction "2_2") (pintype "passive"))
      (node (ref "C9") (pin "2") (pinfunction "2_2") (pintype "passive"))
      (node (ref "D7") (pin "2") (pinfunction "A_2") (pintype "passive"))
      (node (ref "J7") (pin "1") (pinfunction "VTREF_1") (pintype "passive"))
      (node (ref "JP6") (pin "1") (pinfunction "1_1") (pintype "passive"))
      (node (ref "JP6") (pin "2") (pinfunction "2_2") (pintype "passive"))
      (node (ref "L2") (pin "2") (pinfunction "2_2") (pintype "passive"))
      (node (ref "Q1") (pin "4") (pinfunction "S_4") (pintype "passive"))
      (node (ref "R12") (pin "2") (pinfunction "2_2") (pintype "passive"))
      (node (ref "R13") (pin "1") (pinfunction "1_1") (pintype "passive"))
      (node (ref "R14") (pin "10") (pinfunction "55_10") (pintype "passive"))
      (node (ref "R14") (pin "5") (pinfunction "55_5") (pintype "passive"))
      (node (ref "R15") (pin "10") (pinfunction "55_10") (pintype "passive"))
      (node (ref "R15") (pin "5") (pinfunction "55_5") (pintype "passive"))
      (node (ref "R16") (pin "2") (pinfunction "2_2") (pintype "passive"))
      (node (ref "R2") (pin "2") (pinfunction "2_2") (pintype "passive"))
      (node (ref "R27") (pin "2") (pinfunction "2_2") (pintype "passive"))
      (node (ref "R32") (pin "1") (pinfunction "1_1") (pintype "passive"))
      (node (ref "R33") (pin "2") (pinfunction "2_2") (pintype "passive"))
      (node (ref "R39") (pin "1") (pinfunction "1_1") (pintype "passive"))
      (node (ref "R40") (pin "2") (pinfunction "2_2") (pintype "passive"))
      (node (ref "TP17") (pin "1") (pinfunction "1_1") (pintype "passive"))
      (node (ref "TP9") (pin "1") (pinfunction "1_1") (pintype "passive"))
      (node (ref "U2") (pin "3") (pinfunction "VCC_3") (pintype "power_in"))
      (node (ref "U3") (pin "3") (pinfunction "VCC_3") (pintype "power_in"))
      (node (ref "U5") (pin "10") (pinfunction "FB_10") (pintype "input"))
      (node (ref "U7") (pin "1") (pinfunction "VBAT_1") (pintype "power_in"))
      (node (ref "U7") (pin "13") (pinfunction "VDDA_13") (pintype "power_in"))
      (node (ref "U7") (pin "19") (pinfunction "VDD_19") (pintype "power_in"))
      (node (ref "U7") (pin "32") (pinfunction "VDD_32") (pintype "power_in"))
      (node (ref "U7") (pin "48") (pinfunction "VDD_48") (pintype "power_in"))
      (node (ref "U7") (pin "64") (pinfunction "VDD_64") (pintype "power_in"))
    )
    (net (code "2") (name "AUX-1") (class "Default")
      (node (ref "J1") (pin "1") (pinfunction "1_1") (pintype "passive"))
      (node (ref "J1") (pin "2") (pinfunction "2_2") (pintype "passive"))
      (node (ref "JP9") (pin "1") (pinfunction "1_1") (pintype "passive"))
    )
    (net (code "3") (name "AUX-2") (class "Default")
      (node (ref "J1") (pin "3") (pinfunction "3_3") (pintype "passive"))
      (node (ref "J1") (pin "4") (pinfunction "4_4") (pintype "passive"))
      (node (ref "JP9") (pin "2") (pinfunction "2_2") (pintype "passive"))
    )
    (net (code "4") (name "AUX-3") (class "Default")
      (node (ref "J1") (pin "5") (pinfunction "5_5") (pintype "passive"))
      (node (ref "J1") (pin "6") (pinfunction "6_6") (pintype "passive"))
      (node (ref "JP9") (pin "3") (pinfunction "3_3") (pintype "passive"))
    )
    (net (code "5") (name "AUX-4") (class "Default")
      (node (ref "J1") (pin "7") (pinfunction "7_7") (pintype "passive"))
      (node (ref "J1") (pin "8") (pinfunction "8_8") (pintype "passive"))
      (node (ref "JP9") (pin "4") (pinfunction "4_4") (pintype "passive"))
    )
    (net (code "6") (name "AUX-5") (class "Default")
      (node (ref "J1") (pin "10") (pinfunction "10_10") (pintype "passive"))
      (node (ref "J1") (pin "9") (pinfunction "9_9") (pintype "passive"))
      (node (ref "JP9") (pin "5") (pinfunction "5_5") (pintype "passive"))
    )
    (net (code "7") (name "AUX-6") (class "Default")
      (node (ref "J1") (pin "11") (pinfunction "11_11") (pintype "passive"))
      (node (ref "J1") (pin "12") (pinfunction "12_12") (pintype "passive"))
      (node (ref "JP9") (pin "6") (pinfunction "6_6") (pintype "passive"))
    )
    (net (code "8") (name "AUX-7") (class "Default")
      (node (ref "J1") (pin "13") (pinfunction "13_13") (pintype "passive"))
      (node (ref "J1") (pin "14") (pinfunction "14_14") (pintype "passive"))
      (node (ref "JP9") (pin "7") (pinfunction "7_7") (pintype "passive"))
    )
    (net (code "9") (name "AUX-8") (class "Default")
      (node (ref "J1") (pin "15") (pinfunction "15_15") (pintype "passive"))
      (node (ref "J1") (pin "16") (pinfunction "16_16") (pintype "passive"))
      (node (ref "JP9") (pin "8") (pinfunction "8_8") (pintype "passive"))
    )
    (net (code "10") (name "AUX-9") (class "Default")
      (node (ref "J1") (pin "17") (pinfunction "17_17") (pintype "passive"))
      (node (ref "J1") (pin "18") (pinfunction "18_18") (pintype "passive"))
      (node (ref "JP9") (pin "9") (pinfunction "9_9") (pintype "passive"))
    )
    (net (code "11") (name "AUX_~{SHUTDOWN}") (class "Default")
      (node (ref "J1") (pin "19") (pinfunction "19_19") (pintype "passive"))
      (node (ref "J1") (pin "20") (pinfunction "20_20") (pintype "passive"))
      (node (ref "JP9") (pin "10") (pinfunction "10_10") (pintype "passive"))
    )
    (net (code "12") (name "CAN1_H") (class "Default")
      (node (ref "J6") (pin "33") (pinfunction "33_33") (pintype "passive"))
      (node (ref "J6") (pin "34") (pinfunction "34_34") (pintype "passive"))
      (node (ref "JP10") (pin "5") (pinfunction "5_5") (pintype "passive"))
      (node (ref "JP10") (pin "6") (pinfunction "6_6") (pintype "passive"))
      (node (ref "U2") (pin "7") (pinfunction "CANH_7") (pintype "bidirectional"))
    )
    (net (code "13") (name "CAN1_L") (class "Default")
      (node (ref "J6") (pin "35") (pinfunction "35_35") (pintype "passive"))
      (node (ref "J6") (pin "36") (pinfunction "36_36") (pintype "passive"))
      (node (ref "JP10") (pin "7") (pinfunction "7_7") (pintype "passive"))
      (node (ref "JP10") (pin "8") (pinfunction "8_8") (pintype "passive"))
      (node (ref "U2") (pin "6") (pinfunction "CANL_6") (pintype "bidirectional"))
    )
    (net (code "14") (name "CAN1_RX") (class "Default")
      (node (ref "U2") (pin "4") (pinfunction "RXD_4") (pintype "output"))
      (node (ref "U7") (pin "44") (pinfunction "PA11_44") (pintype "bidirectional"))
    )
    (net (code "15") (name "CAN1_SHDN") (class "Default")
      (node (ref "U2") (pin "5") (pinfunction "SHDN_5") (pintype "input"))
      (node (ref "U7") (pin "43") (pinfunction "PA10_43") (pintype "bidirectional"))
    )
    (net (code "16") (name "CAN1_SILENT") (class "Default")
      (node (ref "U2") (pin "8") (pinfunction "S_8") (pintype "input"))
      (node (ref "U7") (pin "42") (pinfunction "PA9_42") (pintype "bidirectional"))
    )
    (net (code "17") (name "CAN1_TX") (class "Default")
      (node (ref "U2") (pin "1") (pinfunction "TXD_1") (pintype "input"))
      (node (ref "U7") (pin "45") (pinfunction "PA12_45") (pintype "bidirectional"))
    )
    (net (code "18") (name "CAN2_H") (class "Default")
      (node (ref "J6") (pin "17") (pinfunction "17_17") (pintype "passive"))
      (node (ref "J6") (pin "18") (pinfunction "18_18") (pintype "passive"))
      (node (ref "JP1") (pin "7") (pinfunction "7_7") (pintype "passive"))
      (node (ref "JP1") (pin "8") (pinfunction "8_8") (pintype "passive"))
      (node (ref "U3") (pin "7") (pinfunction "CANH_7") (pintype "bidirectional"))
    )
    (net (code "19") (name "CAN2_L") (class "Default")
      (node (ref "J6") (pin "19") (pinfunction "19_19") (pintype "passive"))
      (node (ref "J6") (pin "20") (pinfunction "20_20") (pintype "passive"))
      (node (ref "JP1") (pin "10") (pinfunction "10_10") (pintype "passive"))
      (node (ref "JP1") (pin "9") (pinfunction "9_9") (pintype "passive"))
      (node (ref "U3") (pin "6") (pinfunction "CANL_6") (pintype "bidirectional"))
    )
    (net (code "20") (name "CAN2_RX") (class "Default")
      (node (ref "U3") (pin "4") (pinfunction "RXD_4") (pintype "output"))
      (node (ref "U7") (pin "57") (pinfunction "PB5_57") (pintype "bidirectional"))
    )
    (net (code "21") (name "CAN2_SHDN") (class "Default")
      (node (ref "U3") (pin "5") (pinfunction "SHDN_5") (pintype "input"))
      (node (ref "U7") (pin "56") (pinfunction "PB4_56") (pintype "bidirectional"))
    )
    (net (code "22") (name "CAN2_SILENT") (class "Default")
      (node (ref "U3") (pin "8") (pinfunction "S_8") (pintype "input"))
      (node (ref "U7") (pin "59") (pinfunction "PB7_59") (pintype "bidirectional"))
    )
    (net (code "23") (name "CAN2_TX") (class "Default")
      (node (ref "U3") (pin "1") (pinfunction "TXD_1") (pintype "input"))
      (node (ref "U7") (pin "58") (pinfunction "PB6_58") (pintype "bidirectional"))
    )
    (net (code "24") (name "CB_IOUT") (class "Default")
      (node (ref "R20") (pin "1") (pinfunction "1_1") (pintype "passive"))
      (node (ref "R6") (pin "2") (pinfunction "2_2") (pintype "passive"))
      (node (ref "TP10") (pin "1") (pinfunction "1_1") (pintype "passive"))
      (node (ref "U4") (pin "7") (pinfunction "ILIM_7") (pintype "bidirectional"))
    )
    (net (code "25") (name "CB_IOUT_IN") (class "Default")
      (node (ref "R20") (pin "2") (pinfunction "2_2") (pintype "passive"))
      (node (ref "U7") (pin "26") (pinfunction "PB0_26") (pintype "bidirectional"))
    )
    (net (code "26") (name "GND") (class "Default")
      (node (ref "C1") (pin "2") (pinfunction "2_2") (pintype "passive"))
      (node (ref "C10") (pin "2") (pinfunction "2_2") (pintype "passive"))
      (node (ref "C11") (pin "2") (pinfunction "2_2") (pintype "passive"))
      (node (ref "C12") (pin "2") (pinfunction "2_2") (pintype "passive"))
      (node (ref "C13") (pin "1") (pinfunction "1_1") (pintype "passive"))
      (node (ref "C14") (pin "2") (pinfunction "2_2") (pintype "passive"))
      (node (ref "C15") (pin "2") (pinfunction "2_2") (pintype "passive"))
      (node (ref "C16") (pin "2") (pinfunction "2_2") (pintype "passive"))
      (node (ref "C17") (pin "1") (pinfunction "1_1") (pintype "passive"))
      (node (ref "C18") (pin "2") (pinfunction "2_2") (pintype "passive"))
      (node (ref "C19") (pin "2") (pinfunction "2_2") (pintype "passive"))
      (node (ref "C2") (pin "1") (pinfunction "1_1") (pintype "passive"))
      (node (ref "C21") (pin "2") (pinfunction "2_2") (pintype "passive"))
      (node (ref "C22") (pin "1") (pinfunction "1_1") (pintype "passive"))
      (node (ref "C23") (pin "2") (pinfunction "2_2") (pintype "passive"))
      (node (ref "C24") (pin "2") (pinfunction "2_2") (pintype "passive"))
      (node (ref "C25") (pin "2") (pinfunction "2_2") (pintype "passive"))
      (node (ref "C26") (pin "2") (pinfunction "2_2") (pintype "passive"))
      (node (ref "C3") (pin "1") (pinfunction "1_1") (pintype "passive"))
      (node (ref "C4") (pin "2") (pinfunction "2_2") (pintype "passive"))
      (node (ref "C43") (pin "1") (pinfunction "1_1") (pintype "passive"))
      (node (ref "C44") (pin "2") (pinfunction "2_2") (pintype "passive"))
      (node (ref "C46") (pin "2") (pinfunction "2_2") (pintype "passive"))
      (node (ref "C47") (pin "1") (pinfunction "1_1") (pintype "passive"))
      (node (ref "C5") (pin "2") (pinfunction "2_2") (pintype "passive"))
      (node (ref "C50") (pin "2") (pinfunction "2_2") (pintype "passive"))
      (node (ref "C51") (pin "2") (pinfunction "2_2") (pintype "passive"))
      (node (ref "C52") (pin "2") (pinfunction "2_2") (pintype "passive"))
      (node (ref "C53") (pin "2") (pinfunction "2_2") (pintype "passive"))
      (node (ref "C54") (pin "2") (pinfunction "2_2") (pintype "passive"))
      (node (ref "C55") (pin "2") (pinfunction "2_2") (pintype "passive"))
      (node (ref "C56") (pin "2") (pinfunction "2_2") (pintype "passive"))
      (node (ref "C57") (pin "2") (pinfunction "2_2") (pintype "passive"))
      (node (ref "C59") (pin "1") (pinfunction "1_1") (pintype "passive"))
      (node (ref "C6") (pin "1") (pinfunction "1_1") (pintype "passive"))
      (node (ref "C60") (pin "2") (pinfunction "2_2") (pintype "passive"))
      (node (ref "C62") (pin "2") (pinfunction "2_2") (pintype "passive"))
      (node (ref "C63") (pin "1") (pinfunction "1_1") (pintype "passive"))
      (node (ref "C66") (pin "2") (pinfunction "2_2") (pintype "passive"))
      (node (ref "C67") (pin "2") (pinfunction "2_2") (pintype "passive"))
      (node (ref "C68") (pin "2") (pinfunction "2_2") (pintype "passive"))
      (node (ref "C69") (pin "2") (pinfunction "2_2") (pintype "passive"))
      (node (ref "C7") (pin "2") (pinfunction "2_2") (pintype "passive"))
      (node (ref "C70") (pin "2") (pinfunction "2_2") (pintype "passive"))
      (node (ref "C71") (pin "2") (pinfunction "2_2") (pintype "passive"))
      (node (ref "C72") (pin "2") (pinfunction "2_2") (pintype "passive"))
      (node (ref "C73") (pin "2") (pinfunction "2_2") (pintype "passive"))
      (node (ref "C8") (pin "1") (pinfunction "1_1") (pintype "passive"))
      (node (ref "C9") (pin "1") (pinfunction "1_1") (pintype "passive"))
      (node (ref "CM1") (pin "P$1") (pinfunction "SHIELD3_P$1") (pintype "passive"))
      (node (ref "CM1") (pin "P$2") (pinfunction "SHIELD2_P$2") (pintype "passive"))
      (node (ref "CM1") (pin "P$3") (pinfunction "SHIELD1_P$3") (pintype "passive"))
      (node (ref "CM1") (pin "P$4") (pinfunction "SHIELD_P$4") (pintype "passive"))
      (node (ref "CM2") (pin "P$1") (pinfunction "SHIELD3_P$1") (pintype "passive"))
      (node (ref "CM2") (pin "P$2") (pinfunction "SHIELD2_P$2") (pintype "passive"))
      (node (ref "CM2") (pin "P$3") (pinfunction "SHIELD1_P$3") (pintype "passive"))
      (node (ref "CM2") (pin "P$4") (pinfunction "SHIELD_P$4") (pintype "passive"))
      (node (ref "CM3") (pin "P$1") (pinfunction "SHIELD3_P$1") (pintype "passive"))
      (node (ref "CM3") (pin "P$2") (pinfunction "SHIELD2_P$2") (pintype "passive"))
      (node (ref "CM3") (pin "P$3") (pinfunction "SHIELD1_P$3") (pintype "passive"))
      (node (ref "CM3") (pin "P$4") (pinfunction "SHIELD_P$4") (pintype "passive"))
      (node (ref "D1") (pin "C") (pinfunction "C_C") (pintype "passive"))
      (node (ref "D2") (pin "C") (pinfunction "C_C") (pintype "passive"))
      (node (ref "D3") (pin "C") (pinfunction "C_C") (pintype "passive"))
      (node (ref "D5") (pin "C") (pinfunction "C_C") (pintype "passive"))
      (node (ref "J10") (pin "1") (pinfunction "GND_1") (pintype "bidirectional"))
      (node (ref "J10") (pin "2") (pinfunction "GND_2") (pintype "bidirectional"))
      (node (ref "J11") (pin "1") (pinfunction "GND_1") (pintype "bidirectional"))
      (node (ref "J11") (pin "2") (pinfunction "GND_2") (pintype "bidirectional"))
      (node (ref "J13") (pin "1") (pinfunction "GND_1") (pintype "bidirectional"))
      (node (ref "J13") (pin "2") (pinfunction "GND_2") (pintype "bidirectional"))
      (node (ref "J14") (pin "1") (pinfunction "GND_1") (pintype "bidirectional"))
      (node (ref "J14") (pin "2") (pinfunction "GND_2") (pintype "bidirectional"))
      (node (ref "J15") (pin "13") (pinfunction "13_13") (pintype "passive"))
      (node (ref "J15") (pin "14") (pinfunction "14_14") (pintype "passive"))
      (node (ref "J15") (pin "15") (pinfunction "15_15") (pintype "passive"))
      (node (ref "J15") (pin "16") (pinfunction "16_16") (pintype "passive"))
      (node (ref "J19") (pin "13") (pinfunction "13_13") (pintype "passive"))
      (node (ref "J19") (pin "14") (pinfunction "14_14") (pintype "passive"))
      (node (ref "J19") (pin "15") (pinfunction "15_15") (pintype "passive"))
      (node (ref "J19") (pin "16") (pinfunction "16_16") (pintype "passive"))
      (node (ref "J2") (pin "1") (pinfunction "GND_1") (pintype "bidirectional"))
      (node (ref "J2") (pin "2") (pinfunction "GND_2") (pintype "bidirectional"))
      (node (ref "J3") (pin "1") (pinfunction "GND_1") (pintype "bidirectional"))
      (node (ref "J3") (pin "2") (pinfunction "GND_2") (pintype "bidirectional"))
      (node (ref "J4") (pin "1") (pinfunction "GND_1") (pintype "bidirectional"))
      (node (ref "J4") (pin "2") (pinfunction "GND_2") (pintype "bidirectional"))
      (node (ref "J6") (pin "27") (pinfunction "27_27") (pintype "passive"))
      (node (ref "J6") (pin "28") (pinfunction "28_28") (pintype "passive"))
      (node (ref "J6") (pin "29") (pinfunction "29_29") (pintype "passive"))
      (node (ref "J6") (pin "30") (pinfunction "30_30") (pintype "passive"))
      (node (ref "J6") (pin "31") (pinfunction "31_31") (pintype "passive"))
      (node (ref "J6") (pin "32") (pinfunction "32_32") (pintype "passive"))
      (node (ref "J6") (pin "37") (pinfunction "37_37") (pintype "passive"))
      (node (ref "J6") (pin "38") (pinfunction "38_38") (pintype "passive"))
      (node (ref "J7") (pin "3") (pinfunction "GND_3") (pintype "passive"))
      (node (ref "J7") (pin "5") (pinfunction "GND_5") (pintype "passive"))
      (node (ref "J7") (pin "9") (pinfunction "GNDDET_9") (pintype "passive"))
      (node (ref "J8") (pin "1") (pinfunction "GND_1") (pintype "bidirectional"))
      (node (ref "J8") (pin "2") (pinfunction "GND_2") (pintype "bidirectional"))
      (node (ref "J9") (pin "1") (pinfunction "GND_1") (pintype "bidirectional"))
      (node (ref "J9") (pin "2") (pinfunction "GND_2") (pintype "bidirectional"))
      (node (ref "JP2") (pin "10") (pinfunction "10_10") (pintype "passive"))
      (node (ref "JP2") (pin "7") (pinfunction "7_7") (pintype "passive"))
      (node (ref "JP2") (pin "8") (pinfunction "8_8") (pintype "passive"))
      (node (ref "JP2") (pin "9") (pinfunction "9_9") (pintype "passive"))
      (node (ref "L11") (pin "1") (pinfunction "1_1") (pintype "passive"))
      (node (ref "L12") (pin "2") (pinfunction "2_2") (pintype "passive"))
      (node (ref "L13") (pin "1") (pinfunction "1_1") (pintype "passive"))
      (node (ref "L7") (pin "1") (pinfunction "1_1") (pintype "passive"))
      (node (ref "L8") (pin "2") (pinfunction "2_2") (pintype "passive"))
      (node (ref "L9") (pin "1") (pinfunction "1_1") (pintype "passive"))
      (node (ref "R10") (pin "1") (pinfunction "1_1") (pintype "passive"))
      (node (ref "R17") (pin "1") (pinfunction "1_1") (pintype "passive"))
      (node (ref "R36") (pin "1") (pinfunction "1_1") (pintype "passive"))
      (node (ref "R6") (pin "1") (pinfunction "1_1") (pintype "passive"))
      (node (ref "R9") (pin "1") (pinfunction "1_1") (pintype "passive"))
      (node (ref "TP11") (pin "1") (pinfunction "1_1") (pintype "passive"))
      (node (ref "U$2") (pin "P$6") (pinfunction "GND_P$6") (pintype "passive"))
      (node (ref "U1") (pin "4") (pinfunction "GND_4") (pintype "power_in"))
      (node (ref "U11") (pin "2") (pinfunction "GND1_2") (pintype "power_in"))
      (node (ref "U11") (pin "25") (pinfunction "GPADC1_25") (pintype "input"))
      (node (ref "U11") (pin "26") (pinfunction "GPADC2_26") (pintype "input"))
      (node (ref "U11") (pin "6") (pinfunction "GND2_6") (pintype "power_in"))
      (node (ref "U11") (pin "PAD") (pinfunction "PGND_PAD") (pintype "power_in"))
      (node (ref "U12") (pin "2") (pinfunction "GND_2") (pintype "power_in"))
      (node (ref "U13") (pin "2") (pinfunction "GND1_2") (pintype "power_in"))
      (node (ref "U13") (pin "25") (pinfunction "GPADC1_25") (pintype "input"))
      (node (ref "U13") (pin "26") (pinfunction "GPADC2_26") (pintype "input"))
      (node (ref "U13") (pin "6") (pinfunction "GND2_6") (pintype "power_in"))
      (node (ref "U13") (pin "PAD") (pinfunction "PGND_PAD") (pintype "power_in"))
      (node (ref "U14") (pin "2") (pinfunction "GND_2") (pintype "power_in"))
      (node (ref "U2") (pin "2") (pinfunction "GND_2") (pintype "power_in"))
      (node (ref "U3") (pin "2") (pinfunction "GND_2") (pintype "power_in"))
      (node (ref "U4") (pin "1") (pinfunction "GND_1") (pintype "bidirectional"))
      (node (ref "U4") (pin "THERMAL") (pinfunction "GND_THERMAL") (pintype "bidirectional"))
      (node (ref "U5") (pin "1") (pinfunction "GND_1") (pintype "power_in"))
      (node (ref "U5") (pin "11") (pinfunction "GND_11") (pintype "power_in"))
      (node (ref "U5") (pin "12") (pinfunction "GND_12") (pintype "power_in"))
      (node (ref "U5") (pin "16") (pinfunction "GND_16") (pintype "power_in"))
      (node (ref "U5") (pin "6") (pinfunction "LBO_6") (pintype "open_collector"))
      (node (ref "U5") (pin "7") (pinfunction "LBI_7") (pintype "input"))
      (node (ref "U5") (pin "9") (pinfunction "GND_9") (pintype "power_in"))
      (node (ref "U5") (pin "PAD") (pinfunction "GND_PAD") (pintype "power_in"))
      (node (ref "U6") (pin "2") (pinfunction "GND_2") (pintype "power_in"))
      (node (ref "U6") (pin "5") (pinfunction "SET1_5") (pintype "input"))
      (node (ref "U6") (pin "6") (pinfunction "SET2_6") (pintype "input"))
      (node (ref "U7") (pin "12") (pinfunction "VSSA_12") (pintype "power_in"))
      (node (ref "U7") (pin "18") (pinfunction "VSS_18") (pintype "power_in"))
      (node (ref "U7") (pin "31") (pinfunction "VSS_31") (pintype "power_in"))
      (node (ref "U7") (pin "47") (pinfunction "VSS_47") (pintype "power_in"))
      (node (ref "U7") (pin "63") (pinfunction "VSS_63") (pintype "power_in"))
      (node (ref "U9") (pin "A6") (pinfunction "VSSIO_A6") (pintype "power_in"))
      (node (ref "U9") (pin "C4") (pinfunction "VSSQ_C4") (pintype "power_in"))
      (node (ref "U9") (pin "D4") (pinfunction "VSSIO_D4") (pintype "power_in"))
      (node (ref "U9") (pin "E7") (pinfunction "VSSIO_E7") (pintype "power_in"))
      (node (ref "U9") (pin "G5") (pinfunction "VSSIO_G5") (pintype "power_in"))
      (node (ref "U9") (pin "H10") (pinfunction "VSSIO_H10") (pintype "power_in"))
      (node (ref "U9") (pin "J5") (pinfunction "VSSIO_J5") (pintype "power_in"))
      (node (ref "U9") (pin "K8") (pinfunction "VSSIO_K8") (pintype "power_in"))
      (node (ref "U9") (pin "N1") (pinfunction "VSSQ_N1") (pintype "power_in"))
      (node (ref "U9") (pin "N2") (pinfunction "VSSQ_N2") (pintype "power_in"))
      (node (ref "U9") (pin "N5") (pinfunction "VSSQ_N5") (pintype "power_in"))
      (node (ref "U9") (pin "P4") (pinfunction "VSSQ_P4") (pintype "power_in"))
      (node (ref "U9") (pin "P6") (pinfunction "VSSQ_P6") (pintype "power_in"))
      (node (ref "X1") (pin "2") (pinfunction "SHIELD_2") (pintype "power_in"))
      (node (ref "X1") (pin "4") (pinfunction "SHIELD_4") (pintype "power_in"))
      (node (ref "X3") (pin "2") (pinfunction "GND_2") (pintype "power_in"))
      (node (ref "X4") (pin "2") (pinfunction "GND_2") (pintype "power_in"))
    )
    (net (code "27") (name "MMC_PWR") (class "Default")
      (node (ref "Q1") (pin "3") (pinfunction "G_3") (pintype "passive"))
      (node (ref "R14") (pin "1") (pinfunction "11_1") (pintype "passive"))
      (node (ref "U7") (pin "2") (pinfunction "PC13_2") (pintype "bidirectional"))
    )
    (net (code "28") (name "MMC_VDD") (class "Default")
      (node (ref "C23") (pin "1") (pinfunction "1_1") (pintype "passive"))
      (node (ref "C24") (pin "1") (pinfunction "1_1") (pintype "passive"))
      (node (ref "C25") (pin "1") (pinfunction "1_1") (pintype "passive"))
      (node (ref "C26") (pin "1") (pinfunction "1_1") (pintype "passive"))
      (node (ref "Q1") (pin "1") (pinfunction "D_1") (pintype "passive"))
      (node (ref "Q1") (pin "2") (pinfunction "D_2") (pintype "passive"))
      (node (ref "Q1") (pin "5") (pinfunction "D_5") (pintype "passive"))
      (node (ref "Q1") (pin "6") (pinfunction "D_6") (pintype "passive"))
      (node (ref "U9") (pin "C6") (pinfunction "VDDQ_C6") (pintype "power_in"))
      (node (ref "U9") (pin "E6") (pinfunction "VDDIO_E6") (pintype "power_in"))
      (node (ref "U9") (pin "F5") (pinfunction "VDDIO_F5") (pintype "power_in"))
      (node (ref "U9") (pin "J10") (pinfunction "VDDIO_J10") (pintype "power_in"))
      (node (ref "U9") (pin "K9") (pinfunction "VDDIO_K9") (pintype "power_in"))
      (node (ref "U9") (pin "M4") (pinfunction "VDDQ_M4") (pintype "power_in"))
      (node (ref "U9") (pin "N4") (pinfunction "VDDQ_N4") (pintype "power_in"))
      (node (ref "U9") (pin "P3") (pinfunction "VDDQ_P3") (pintype "power_in"))
      (node (ref "U9") (pin "P5") (pinfunction "VDDQ_P5") (pintype "power_in"))
    )
    (net (code "29") (name "NRST") (class "Default")
      (node (ref "J7") (pin "10") (pinfunction "~{RESET}_10") (pintype "passive"))
      (node (ref "TP2") (pin "1") (pinfunction "1_1") (pintype "passive"))
      (node (ref "U7") (pin "7") (pinfunction "NRST_7") (pintype "bidirectional"))
    )
    (net (code "30") (name "Net-(C42-Pad1)") (class "Default")
      (node (ref "C42") (pin "1") (pinfunction "1_1") (pintype "passive"))
      (node (ref "C48") (pin "2") (pinfunction "2_2") (pintype "passive"))
      (node (ref "L6") (pin "1") (pinfunction "1_1") (pintype "passive"))
    )
    (net (code "31") (name "Net-(C58-Pad1)") (class "Default")
      (node (ref "C58") (pin "1") (pinfunction "1_1") (pintype "passive"))
      (node (ref "C64") (pin "2") (pinfunction "2_2") (pintype "passive"))
      (node (ref "L10") (pin "1") (pinfunction "1_1") (pintype "passive"))
    )
    (net (code "32") (name "Net-(CM1-CENTER)") (class "Default")
      (node (ref "CM1") (pin "RF") (pinfunction "CENTER_RF") (pintype "passive"))
      (node (ref "J2") (pin "FEED") (pinfunction "SIGNAL_FEED") (pintype "bidirectional"))
    )
    (net (code "33") (name "Net-(CM2-CENTER)") (class "Default")
      (node (ref "CM2") (pin "RF") (pinfunction "CENTER_RF") (pintype "passive"))
      (node (ref "J3") (pin "FEED") (pinfunction "SIGNAL_FEED") (pintype "bidirectional"))
    )
    (net (code "34") (name "Net-(CM3-CENTER)") (class "Default")
      (node (ref "CM3") (pin "RF") (pinfunction "CENTER_RF") (pintype "passive"))
      (node (ref "J4") (pin "FEED") (pinfunction "SIGNAL_FEED") (pintype "bidirectional"))
    )
    (net (code "35") (name "Net-(D1-PadA)") (class "Default")
      (node (ref "D1") (pin "A") (pinfunction "A_A") (pintype "passive"))
      (node (ref "R1") (pin "1") (pinfunction "1_1") (pintype "passive"))
    )
    (net (code "36") (name "Net-(D2-PadA)") (class "Default")
      (node (ref "D2") (pin "A") (pinfunction "A_A") (pintype "passive"))
      (node (ref "R2") (pin "1") (pinfunction "1_1") (pintype "passive"))
    )
    (net (code "37") (name "Net-(D3-PadA)") (class "Default")
      (node (ref "D3") (pin "A") (pinfunction "A_A") (pintype "passive"))
      (node (ref "R3") (pin "1") (pinfunction "1_1") (pintype "passive"))
    )
    (net (code "38") (name "Net-(D4-PadA)") (class "Default")
      (node (ref "D4") (pin "A") (pinfunction "A_A") (pintype "passive"))
      (node (ref "R27") (pin "1") (pinfunction "1_1") (pintype "passive"))
    )
    (net (code "39") (name "Net-(D5-PadA)") (class "Default")
      (node (ref "D5") (pin "A") (pinfunction "A_A") (pintype "passive"))
      (node (ref "R4") (pin "1") (pinfunction "1_1") (pintype "passive"))
    )
    (net (code "40") (name "Net-(D7-C)") (class "Default")
      (node (ref "D7") (pin "1") (pinfunction "C_1") (pintype "passive"))
      (node (ref "R19") (pin "2") (pinfunction "2_2") (pintype "passive"))
    )
    (net (code "41") (name "Net-(J9-SIGNAL)") (class "Default")
      (node (ref "C49") (pin "1") (pinfunction "1_1") (pintype "passive"))
      (node (ref "J9") (pin "FEED") (pinfunction "SIGNAL_FEED") (pintype "bidirectional"))
    )
    (net (code "42") (name "Net-(J10-SIGNAL)") (class "Default")
      (node (ref "C48") (pin "1") (pinfunction "1_1") (pintype "passive"))
      (node (ref "J10") (pin "FEED") (pinfunction "SIGNAL_FEED") (pintype "bidirectional"))
    )
    (net (code "43") (name "Net-(J11-SIGNAL)") (class "Default")
      (node (ref "C64") (pin "1") (pinfunction "1_1") (pintype "passive"))
      (node (ref "J11") (pin "FEED") (pinfunction "SIGNAL_FEED") (pintype "bidirectional"))
    )
    (net (code "44") (name "Net-(J13-SIGNAL)") (class "Default")
      (node (ref "C65") (pin "1") (pinfunction "1_1") (pintype "passive"))
      (node (ref "J13") (pin "FEED") (pinfunction "SIGNAL_FEED") (pintype "bidirectional"))
    )
    (net (code "45") (name "Net-(J14-SIGNAL)") (class "Default")
      (node (ref "J14") (pin "FEED") (pinfunction "SIGNAL_FEED") (pintype "bidirectional"))
      (node (ref "U13") (pin "13") (pinfunction "SYSCLK_13") (pintype "bidirectional"))
    )
    (net (code "46") (name "Net-(L2-Pad1)") (class "Default")
      (node (ref "L2") (pin "1") (pinfunction "1_1") (pintype "passive"))
      (node (ref "U5") (pin "14") (pinfunction "SW_14") (pintype "output"))
      (node (ref "U5") (pin "15") (pinfunction "SW_15") (pintype "output"))
    )
    (net (code "47") (name "Net-(U$2-VCC)") (class "Default")
      (node (ref "JP8") (pin "2") (pinfunction "2_2") (pintype "passive"))
      (node (ref "U$2") (pin "P$4") (pinfunction "VCC_P$4") (pintype "passive"))
    )
    (net (code "48") (name "Net-(U1-IN)") (class "Default")
      (node (ref "C5") (pin "1") (pinfunction "1_1") (pintype "passive"))
      (node (ref "R12") (pin "1") (pinfunction "1_1") (pintype "passive"))
      (node (ref "U1") (pin "1") (pinfunction "IN_2_1") (pintype "power_in"))
      (node (ref "U1") (pin "2") (pinfunction "IN_2") (pintype "power_in"))
    )
    (net (code "49") (name "Net-(U4-EN{slash}UVLO)") (class "Default")
      (node (ref "R5") (pin "1") (pinfunction "1_1") (pintype "passive"))
      (node (ref "R9") (pin "2") (pinfunction "2_2") (pintype "passive"))
      (node (ref "U4") (pin "3") (pinfunction "EN/UVLO_3") (pintype "bidirectional"))
    )
    (net (code "50") (name "Net-(U4-~{FLT})") (class "Default")
      (node (ref "TP1") (pin "1") (pinfunction "1_1") (pintype "passive"))
      (node (ref "U4") (pin "6") (pinfunction "~{FLT}_6") (pintype "bidirectional"))
    )
    (net (code "51") (name "Net-(U5-PG)") (class "Default")
      (node (ref "TP16") (pin "1") (pinfunction "1_1") (pintype "passive"))
      (node (ref "U5") (pin "13") (pinfunction "PG_13") (pintype "open_collector"))
    )
    (net (code "52") (name "Net-(U5-SYNC)") (class "Default")
      (node (ref "R10") (pin "2") (pinfunction "2_2") (pintype "passive"))
      (node (ref "R7") (pin "1") (pinfunction "1_1") (pintype "passive"))
      (node (ref "TP19") (pin "1") (pinfunction "1_1") (pintype "passive"))
      (node (ref "U5") (pin "5") (pinfunction "SYNC_5") (pintype "input"))
    )
    (net (code "53") (name "Net-(U6-SET0)") (class "Default")
      (node (ref "C15") (pin "1") (pinfunction "1_1") (pintype "passive"))
      (node (ref "C18") (pin "1") (pinfunction "1_1") (pintype "passive"))
      (node (ref "R19") (pin "1") (pinfunction "1_1") (pintype "passive"))
      (node (ref "U6") (pin "4") (pinfunction "SET0_4") (pintype "input"))
      (node (ref "U6") (pin "8") (pinfunction "VCC_8") (pintype "power_in"))
    )
    (net (code "54") (name "Net-(U7-BOOT0)") (class "Default")
      (node (ref "R17") (pin "2") (pinfunction "2_2") (pintype "passive"))
      (node (ref "TP15") (pin "1") (pinfunction "1_1") (pintype "passive"))
      (node (ref "U7") (pin "60") (pinfunction "BOOT0_60") (pintype "bidirectional"))
    )
    (net (code "55") (name "Net-(U7-PH0-OSC_IN)") (class "Default")
      (node (ref "C16") (pin "1") (pinfunction "1_1") (pintype "passive"))
      (node (ref "U7") (pin "5") (pinfunction "PH0-OSC_IN_5") (pintype "bidirectional"))
      (node (ref "X1") (pin "1") (pinfunction "1_1") (pintype "passive"))
    )
    (net (code "56") (name "Net-(U7-PH1-OSC_OUT)") (class "Default")
      (node (ref "C11") (pin "1") (pinfunction "1_1") (pintype "passive"))
      (node (ref "U7") (pin "6") (pinfunction "PH1-OSC_OUT_6") (pintype "bidirectional"))
      (node (ref "X1") (pin "3") (pinfunction "2_3") (pintype "passive"))
    )
    (net (code "57") (name "Net-(U11-ANTN)") (class "Default")
      (node (ref "C42") (pin "2") (pinfunction "2_2") (pintype "passive"))
      (node (ref "L7") (pin "2") (pinfunction "2_2") (pintype "passive"))
      (node (ref "U11") (pin "4") (pinfunction "ANTN_4") (pintype "bidirectional"))
    )
    (net (code "58") (name "Net-(U11-ANTP)") (class "Default")
      (node (ref "C43") (pin "2") (pinfunction "2_2") (pintype "passive"))
      (node (ref "L6") (pin "2") (pinfunction "2_2") (pintype "passive"))
      (node (ref "L8") (pin "1") (pinfunction "1_1") (pintype "passive"))
      (node (ref "U11") (pin "3") (pinfunction "ANTP_3") (pintype "bidirectional"))
    )
    (net (code "59") (name "Net-(U11-ANTP1)") (class "Default")
      (node (ref "C49") (pin "2") (pinfunction "2_2") (pintype "passive"))
      (node (ref "L9") (pin "2") (pinfunction "2_2") (pintype "passive"))
      (node (ref "U11") (pin "5") (pinfunction "ANTP1_5") (pintype "bidirectional"))
    )
    (net (code "60") (name "Net-(U11-CLK16N)") (class "Default")
      (node (ref "C44") (pin "1") (pinfunction "1_1") (pintype "passive"))
      (node (ref "R28") (pin "1") (pinfunction "1_1") (pintype "passive"))
      (node (ref "U11") (pin "27") (pinfunction "CLK16N_27") (pintype "passive"))
    )
    (net (code "61") (name "Net-(U11-CLK16P)") (class "Default")
      (node (ref "C45") (pin "1") (pinfunction "1_1") (pintype "passive"))
      (node (ref "R28") (pin "2") (pinfunction "2_2") (pintype "passive"))
      (node (ref "U11") (pin "28") (pinfunction "CLK16P_28") (pintype "passive"))
    )
    (net (code "62") (name "Net-(U11-CS)") (class "Default")
      (node (ref "J15") (pin "1") (pinfunction "1_1") (pintype "passive"))
      (node (ref "U11") (pin "14") (pinfunction "CS_14") (pintype "input"))
    )
    (net (code "63") (name "Net-(U11-IRQ)") (class "Default")
      (node (ref "J15") (pin "9") (pinfunction "9_9") (pintype "passive"))
      (node (ref "U11") (pin "19") (pinfunction "IRQ_19") (pintype "bidirectional"))
    )
    (net (code "64") (name "Net-(U11-L1)") (class "Default")
      (node (ref "U11") (pin "10") (pinfunction "L1_10") (pintype "input"))
      (node (ref "U11") (pin "9") (pinfunction "L2_9") (pintype "input"))
    )
    (net (code "65") (name "Net-(U11-MISO)") (class "Default")
      (node (ref "J15") (pin "5") (pinfunction "5_5") (pintype "passive"))
      (node (ref "U11") (pin "16") (pinfunction "MISO_16") (pintype "output"))
    )
    (net (code "66") (name "Net-(U11-MOSI)") (class "Default")
      (node (ref "J15") (pin "7") (pinfunction "7_7") (pintype "passive"))
      (node (ref "U11") (pin "17") (pinfunction "MOSI_17") (pintype "input"))
    )
    (net (code "67") (name "Net-(U11-PWRAMP)") (class "Default")
      (node (ref "J15") (pin "11") (pinfunction "11_11") (pintype "passive"))
      (node (ref "U11") (pin "20") (pinfunction "PWRAMP_20") (pintype "bidirectional"))
    )
    (net (code "68") (name "Net-(U11-SCLK)") (class "Default")
      (node (ref "J15") (pin "3") (pinfunction "3_3") (pintype "passive"))
      (node (ref "U11") (pin "15") (pinfunction "SCLK_15") (pintype "input"))
    )
    (net (code "69") (name "Net-(U11-VDD_A1)") (class "Default")
      (node (ref "C46") (pin "1") (pinfunction "1_1") (pintype "passive"))
      (node (ref "U11") (pin "1") (pinfunction "VDD_A1_1") (pintype "power_in"))
    )
    (net (code "70") (name "Net-(U11-VDD_A2)") (class "Default")
      (node (ref "C47") (pin "2") (pinfunction "2_2") (pintype "passive"))
      (node (ref "U11") (pin "7") (pinfunction "VDD_A2_7") (pintype "power_in"))
    )
    (net (code "71") (name "Net-(U11-VDD_IO)") (class "Default")
      (node (ref "C53") (pin "1") (pinfunction "1_1") (pintype "passive"))
      (node (ref "C54") (pin "1") (pinfunction "1_1") (pintype "passive"))
      (node (ref "C55") (pin "1") (pinfunction "1_1") (pintype "passive"))
      (node (ref "R33") (pin "1") (pinfunction "1_1") (pintype "passive"))
      (node (ref "U11") (pin "23") (pinfunction "VDD_IO_23") (pintype "power_in"))
    )
    (net (code "72") (name "Net-(U12-BYPASS)") (class "Default")
      (node (ref "C56") (pin "1") (pinfunction "1_1") (pintype "passive"))
      (node (ref "U12") (pin "4") (pinfunction "BYPASS_4") (pintype "power_in"))
    )
    (net (code "73") (name "Net-(U12-EN)") (class "Default")
      (node (ref "C57") (pin "1") (pinfunction "1_1") (pintype "passive"))
      (node (ref "R32") (pin "2") (pinfunction "2_2") (pintype "passive"))
      (node (ref "U12") (pin "1") (pinfunction "VIN_1") (pintype "power_in"))
      (node (ref "U12") (pin "3") (pinfunction "EN_3") (pintype "input"))
    )
    (net (code "74") (name "Net-(U12-VOUT)") (class "Default")
      (node (ref "C50") (pin "1") (pinfunction "1_1") (pintype "passive"))
      (node (ref "C51") (pin "1") (pinfunction "1_1") (pintype "passive"))
      (node (ref "C52") (pin "1") (pinfunction "1_1") (pintype "passive"))
      (node (ref "U12") (pin "5") (pinfunction "VOUT_5") (pintype "power_in"))
      (node (ref "X3") (pin "4") (pinfunction "VDD_4") (pintype "power_in"))
    )
    (net (code "75") (name "Net-(U13-ANTN)") (class "Default")
      (node (ref "C58") (pin "2") (pinfunction "2_2") (pintype "passive"))
      (node (ref "L11") (pin "2") (pinfunction "2_2") (pintype "passive"))
      (node (ref "U13") (pin "4") (pinfunction "ANTN_4") (pintype "bidirectional"))
    )
    (net (code "76") (name "Net-(U13-ANTP)") (class "Default")
      (node (ref "C59") (pin "2") (pinfunction "2_2") (pintype "passive"))
      (node (ref "L10") (pin "2") (pinfunction "2_2") (pintype "passive"))
      (node (ref "L12") (pin "1") (pinfunction "1_1") (pintype "passive"))
      (node (ref "U13") (pin "3") (pinfunction "ANTP_3") (pintype "bidirectional"))
    )
    (net (code "77") (name "Net-(U13-ANTP1)") (class "Default")
      (node (ref "C65") (pin "2") (pinfunction "2_2") (pintype "passive"))
      (node (ref "L13") (pin "2") (pinfunction "2_2") (pintype "passive"))
      (node (ref "U13") (pin "5") (pinfunction "ANTP1_5") (pintype "bidirectional"))
    )
    (net (code "78") (name "Net-(U13-CLK16N)") (class "Default")
      (node (ref "C60") (pin "1") (pinfunction "1_1") (pintype "passive"))
      (node (ref "R34") (pin "1") (pinfunction "1_1") (pintype "passive"))
      (node (ref "U13") (pin "27") (pinfunction "CLK16N_27") (pintype "passive"))
    )
    (net (code "79") (name "Net-(U13-CLK16P)") (class "Default")
      (node (ref "C61") (pin "1") (pinfunction "1_1") (pintype "passive"))
      (node (ref "R34") (pin "2") (pinfunction "2_2") (pintype "passive"))
      (node (ref "U13") (pin "28") (pinfunction "CLK16P_28") (pintype "passive"))
    )
    (net (code "80") (name "Net-(U13-CS)") (class "Default")
      (node (ref "J19") (pin "1") (pinfunction "1_1") (pintype "passive"))
      (node (ref "U13") (pin "14") (pinfunction "CS_14") (pintype "input"))
    )
    (net (code "81") (name "Net-(U13-IRQ)") (class "Default")
      (node (ref "J19") (pin "9") (pinfunction "9_9") (pintype "passive"))
      (node (ref "U13") (pin "19") (pinfunction "IRQ_19") (pintype "bidirectional"))
    )
    (net (code "82") (name "Net-(U13-L1)") (class "Default")
      (node (ref "U13") (pin "10") (pinfunction "L1_10") (pintype "input"))
      (node (ref "U13") (pin "9") (pinfunction "L2_9") (pintype "input"))
    )
    (net (code "83") (name "Net-(U13-MISO)") (class "Default")
      (node (ref "J19") (pin "5") (pinfunction "5_5") (pintype "passive"))
      (node (ref "U13") (pin "16") (pinfunction "MISO_16") (pintype "output"))
    )
    (net (code "84") (name "Net-(U13-MOSI)") (class "Default")
      (node (ref "J19") (pin "7") (pinfunction "7_7") (pintype "passive"))
      (node (ref "U13") (pin "17") (pinfunction "MOSI_17") (pintype "input"))
    )
    (net (code "85") (name "Net-(U13-PWRAMP)") (class "Default")
      (node (ref "J19") (pin "11") (pinfunction "11_11") (pintype "passive"))
      (node (ref "U13") (pin "20") (pinfunction "PWRAMP_20") (pintype "bidirectional"))
    )
    (net (code "86") (name "Net-(U13-SCLK)") (class "Default")
      (node (ref "J19") (pin "3") (pinfunction "3_3") (pintype "passive"))
      (node (ref "U13") (pin "15") (pinfunction "SCLK_15") (pintype "input"))
    )
    (net (code "87") (name "Net-(U13-VDD_A1)") (class "Default")
      (node (ref "C62") (pin "1") (pinfunction "1_1") (pintype "passive"))
      (node (ref "U13") (pin "1") (pinfunction "VDD_A1_1") (pintype "power_in"))
    )
    (net (code "88") (name "Net-(U13-VDD_A2)") (class "Default")
      (node (ref "C63") (pin "2") (pinfunction "2_2") (pintype "passive"))
      (node (ref "U13") (pin "7") (pinfunction "VDD_A2_7") (pintype "power_in"))
    )
    (net (code "89") (name "Net-(U13-VDD_IO)") (class "Default")
      (node (ref "C69") (pin "1") (pinfunction "1_1") (pintype "passive"))
      (node (ref "C70") (pin "1") (pinfunction "1_1") (pintype "passive"))
      (node (ref "C71") (pin "1") (pinfunction "1_1") (pintype "passive"))
      (node (ref "R40") (pin "1") (pinfunction "1_1") (pintype "passive"))
      (node (ref "U13") (pin "23") (pinfunction "VDD_IO_23") (pintype "power_in"))
    )
    (net (code "90") (name "Net-(U14-BYPASS)") (class "Default")
      (node (ref "C72") (pin "1") (pinfunction "1_1") (pintype "passive"))
      (node (ref "U14") (pin "4") (pinfunction "BYPASS_4") (pintype "power_in"))
    )
    (net (code "91") (name "Net-(U14-EN)") (class "Default")
      (node (ref "C73") (pin "1") (pinfunction "1_1") (pintype "passive"))
      (node (ref "R39") (pin "2") (pinfunction "2_2") (pintype "passive"))
      (node (ref "U14") (pin "1") (pinfunction "VIN_1") (pintype "power_in"))
      (node (ref "U14") (pin "3") (pinfunction "EN_3") (pintype "input"))
    )
    (net (code "92") (name "Net-(U14-VOUT)") (class "Default")
      (node (ref "C66") (pin "1") (pinfunction "1_1") (pintype "passive"))
      (node (ref "C67") (pin "1") (pinfunction "1_1") (pintype "passive"))
      (node (ref "C68") (pin "1") (pinfunction "1_1") (pintype "passive"))
      (node (ref "U14") (pin "5") (pinfunction "VOUT_5") (pintype "power_in"))
      (node (ref "X4") (pin "4") (pinfunction "VDD_4") (pintype "power_in"))
    )
    (net (code "93") (name "Net-(X3-OUT)") (class "Default")
      (node (ref "C45") (pin "2") (pinfunction "2_2") (pintype "passive"))
      (node (ref "X3") (pin "3") (pinfunction "OUT_3") (pintype "output"))
    )
    (net (code "94") (name "Net-(X4-OUT)") (class "Default")
      (node (ref "C61") (pin "2") (pinfunction "2_2") (pintype "passive"))
      (node (ref "X4") (pin "3") (pinfunction "OUT_3") (pintype "output"))
    )
    (net (code "95") (name "OPD_ISET") (class "Default")
      (node (ref "R24") (pin "1") (pinfunction "1_1") (pintype "passive"))
      (node (ref "R36") (pin "2") (pinfunction "2_2") (pintype "passive"))
      (node (ref "TP14") (pin "1") (pinfunction "1_1") (pintype "passive"))
      (node (ref "U1") (pin "5") (pinfunction "SET_5") (pintype "input"))
    )
    (net (code "96") (name "OPD_ISET_IN") (class "Default")
      (node (ref "R24") (pin "2") (pinfunction "2_2") (pintype "passive"))
      (node (ref "U7") (pin "27") (pinfunction "PB1_27") (pintype "bidirectional"))
    )
    (net (code "97") (name "OPD_PWR") (class "Default")
      (node (ref "C4") (pin "1") (pinfunction "1_1") (pintype "passive"))
      (node (ref "J6") (pin "15") (pinfunction "15_15") (pintype "passive"))
      (node (ref "J6") (pin "16") (pinfunction "16_16") (pintype "passive"))
      (node (ref "JP1") (pin "5") (pinfunction "5_5") (pintype "passive"))
      (node (ref "JP1") (pin "6") (pinfunction "6_6") (pintype "passive"))
      (node (ref "R11") (pin "1") (pinfunction "1_1") (pintype "passive"))
      (node (ref "R4") (pin "2") (pinfunction "2_2") (pintype "passive"))
      (node (ref "R8") (pin "1") (pinfunction "1_1") (pintype "passive"))
      (node (ref "U1") (pin "7") (pinfunction "OUT_2_7") (pintype "power_in"))
      (node (ref "U1") (pin "8") (pinfunction "OUT_8") (pintype "power_in"))
    )
    (net (code "98") (name "OPD_SCL") (class "Default")
      (node (ref "J6") (pin "13") (pinfunction "13_13") (pintype "passive"))
      (node (ref "J6") (pin "14") (pinfunction "14_14") (pintype "passive"))
      (node (ref "JP1") (pin "3") (pinfunction "3_3") (pintype "passive"))
      (node (ref "JP1") (pin "4") (pinfunction "4_4") (pintype "passive"))
      (node (ref "R8") (pin "2") (pinfunction "2_2") (pintype "passive"))
      (node (ref "U7") (pin "61") (pinfunction "PB8_61") (pintype "bidirectional"))
    )
    (net (code "99") (name "OPD_SDA") (class "Default")
      (node (ref "J6") (pin "11") (pinfunction "11_11") (pintype "passive"))
      (node (ref "J6") (pin "12") (pinfunction "12_12") (pintype "passive"))
      (node (ref "JP1") (pin "1") (pinfunction "1_1") (pintype "passive"))
      (node (ref "JP1") (pin "2") (pinfunction "2_2") (pintype "passive"))
      (node (ref "R11") (pin "2") (pinfunction "2_2") (pintype "passive"))
      (node (ref "U7") (pin "62") (pinfunction "PB9_62") (pintype "bidirectional"))
    )
    (net (code "100") (name "OPD_~{FAULT}") (class "Default")
      (node (ref "R16") (pin "1") (pinfunction "1_1") (pintype "passive"))
      (node (ref "TP8") (pin "1") (pinfunction "1_1") (pintype "passive"))
      (node (ref "U1") (pin "6") (pinfunction "~{FAULT}_6") (pintype "output"))
      (node (ref "U7") (pin "55") (pinfunction "PB3_55") (pintype "bidirectional"))
    )
    (net (code "101") (name "OSC32_IN") (class "Default")
      (node (ref "U7") (pin "3") (pinfunction "PC14-OSC32_IN_3") (pintype "bidirectional"))
    )
    (net (code "102") (name "OSC32_OUT") (class "Default")
      (node (ref "U7") (pin "4") (pinfunction "PC15-OSC32_OUT_4") (pintype "bidirectional"))
    )
    (net (code "103") (name "PA1") (class "Default")
      (node (ref "TP5") (pin "1") (pinfunction "1_1") (pintype "passive"))
      (node (ref "U7") (pin "15") (pinfunction "PA1_15") (pintype "bidirectional"))
    )
    (net (code "104") (name "PA15") (class "Default")
      (node (ref "TP6") (pin "1") (pinfunction "1_1") (pintype "passive"))
      (node (ref "U7") (pin "50") (pinfunction "PA15_50") (pintype "bidirectional"))
    )
    (net (code "105") (name "PB10") (class "Default")
      (node (ref "TP4") (pin "1") (pinfunction "1_1") (pintype "passive"))
      (node (ref "U7") (pin "29") (pinfunction "PB10_29") (pintype "bidirectional"))
    )
    (net (code "106") (name "PB12") (class "Default")
      (node (ref "JP11") (pin "1") (pinfunction "1_1") (pintype "passive"))
      (node (ref "U7") (pin "33") (pinfunction "PB12_33") (pintype "bidirectional"))
    )
    (net (code "107") (name "PC0") (class "Default")
      (node (ref "JP11") (pin "9") (pinfunction "9_9") (pintype "passive"))
      (node (ref "U7") (pin "8") (pinfunction "PC0_8") (pintype "bidirectional"))
    )
    (net (code "108") (name "PC1") (class "Default")
      (node (ref "JP11") (pin "10") (pinfunction "10_10") (pintype "passive"))
      (node (ref "U7") (pin "9") (pinfunction "PC1_9") (pintype "bidirectional"))
    )
    (net (code "109") (name "PC2") (class "Default")
      (node (ref "JP11") (pin "8") (pinfunction "8_8") (pintype "passive"))
      (node (ref "U7") (pin "10") (pinfunction "PC2_10") (pintype "bidirectional"))
    )
    (net (code "110") (name "PC3") (class "Default")
      (node (ref "JP11") (pin "6") (pinfunction "6_6") (pintype "passive"))
      (node (ref "U7") (pin "11") (pinfunction "PC3_11") (pintype "bidirectional"))
    )
    (net (code "111") (name "PC4") (class "Default")
      (node (ref "JP11") (pin "4") (pinfunction "4_4") (pintype "passive"))
      (node (ref "U7") (pin "24") (pinfunction "PC4_24") (pintype "bidirectional"))
    )
    (net (code "112") (name "PC5") (class "Default")
      (node (ref "JP11") (pin "2") (pinfunction "2_2") (pintype "passive"))
      (node (ref "U7") (pin "25") (pinfunction "PC5_25") (pintype "bidirectional"))
    )
    (net (code "113") (name "RADIO1_CS") (class "Default")
      (node (ref "J15") (pin "2") (pinfunction "2_2") (pintype "passive"))
      (node (ref "U7") (pin "37") (pinfunction "PC6_37") (pintype "bidirectional"))
    )
    (net (code "114") (name "RADIO1_IRQ") (class "Default")
      (node (ref "J15") (pin "10") (pinfunction "10_10") (pintype "passive"))
      (node (ref "U7") (pin "20") (pinfunction "PA4_20") (pintype "bidirectional"))
    )
    (net (code "115") (name "RADIO1_PTT") (class "Default")
      (node (ref "J15") (pin "12") (pinfunction "12_12") (pintype "passive"))
    )
    (net (code "116") (name "RADIO2_CS") (class "Default")
      (node (ref "J19") (pin "2") (pinfunction "2_2") (pintype "passive"))
      (node (ref "U7") (pin "38") (pinfunction "PC7_38") (pintype "bidirectional"))
    )
    (net (code "117") (name "RADIO2_IRQ") (class "Default")
      (node (ref "J19") (pin "10") (pinfunction "10_10") (pintype "passive"))
      (node (ref "U7") (pin "41") (pinfunction "PA8_41") (pintype "bidirectional"))
    )
    (net (code "118") (name "RADIO2_PTT") (class "Default")
      (node (ref "J19") (pin "12") (pinfunction "12_12") (pintype "passive"))
    )
    (net (code "119") (name "SDIO_CK") (class "Default")
      (node (ref "R14") (pin "9") (pinfunction "99_9") (pintype "passive"))
      (node (ref "TP7") (pin "1") (pinfunction "1_1") (pintype "passive"))
      (node (ref "U7") (pin "53") (pinfunction "PC12_53") (pintype "bidirectional"))
      (node (ref "U9") (pin "M6") (pinfunction "SCK_M6") (pintype "input"))
    )
    (net (code "120") (name "SDIO_CMD") (class "Default")
      (node (ref "R14") (pin "2") (pinfunction "22_2") (pintype "passive"))
      (node (ref "U7") (pin "54") (pinfunction "PD2_54") (pintype "bidirectional"))
      (node (ref "U9") (pin "M5") (pinfunction "CMD_M5") (pintype "input"))
    )
    (net (code "121") (name "SDIO_D0") (class "Default")
      (node (ref "R15") (pin "1") (pinfunction "11_1") (pintype "passive"))
      (node (ref "U7") (pin "39") (pinfunction "PC8_39") (pintype "bidirectional"))
      (node (ref "U9") (pin "A3") (pinfunction "D0_A3") (pintype "input"))
    )
    (net (code "122") (name "SDIO_D1") (class "Default")
      (node (ref "R15") (pin "9") (pinfunction "99_9") (pintype "passive"))
      (node (ref "U7") (pin "40") (pinfunction "PC9_40") (pintype "bidirectional"))
      (node (ref "U9") (pin "A4") (pinfunction "D1_A4") (pintype "input"))
    )
    (net (code "123") (name "SDIO_D2") (class "Default")
      (node (ref "R15") (pin "2") (pinfunction "22_2") (pintype "passive"))
      (node (ref "U7") (pin "51") (pinfunction "PC10_51") (pintype "bidirectional"))
      (node (ref "U9") (pin "A5") (pinfunction "D2_A5") (pintype "input"))
    )
    (net (code "124") (name "SDIO_D3") (class "Default")
      (node (ref "R14") (pin "7") (pinfunction "77_7") (pintype "passive"))
      (node (ref "U7") (pin "52") (pinfunction "PC11_52") (pintype "bidirectional"))
      (node (ref "U9") (pin "A1") (pinfunction "D3_A1") (pintype "input"))
      (node (ref "U9") (pin "B2") (pinfunction "D3_B2") (pintype "input"))
    )
    (net (code "125") (name "SDIO_D4") (class "Default")
      (node (ref "R14") (pin "6") (pinfunction "66_6") (pintype "passive"))
      (node (ref "U9") (pin "A2") (pinfunction "D4_A2") (pintype "input"))
      (node (ref "U9") (pin "B3") (pinfunction "D4_B3") (pintype "input"))
    )
    (net (code "126") (name "SDIO_D5") (class "Default")
      (node (ref "R14") (pin "8") (pinfunction "88_8") (pintype "passive"))
      (node (ref "U9") (pin "B4") (pinfunction "D5_B4") (pintype "input"))
      (node (ref "U9") (pin "C3") (pinfunction "D5_C3") (pintype "input"))
      (node (ref "U9") (pin "D3") (pinfunction "D5_D3") (pintype "input"))
    )
    (net (code "127") (name "SDIO_D6") (class "Default")
      (node (ref "R14") (pin "4") (pinfunction "44_4") (pintype "passive"))
      (node (ref "U9") (pin "B5") (pinfunction "D6_B5") (pintype "bidirectional"))
      (node (ref "U9") (pin "C5") (pinfunction "D6_C5") (pintype "bidirectional"))
    )
    (net (code "128") (name "SDIO_D7") (class "Default")
      (node (ref "R15") (pin "3") (pinfunction "33_3") (pintype "passive"))
      (node (ref "U9") (pin "B6") (pinfunction "D7_B6") (pintype "input"))
      (node (ref "U9") (pin "C7") (pinfunction "D7_C7") (pintype "input"))
    )
    (net (code "129") (name "SDIO_RST") (class "Default")
      (node (ref "R14") (pin "3") (pinfunction "33_3") (pintype "passive"))
      (node (ref "U9") (pin "K5") (pinfunction "~{RST}_K5") (pintype "input"))
    )
    (net (code "130") (name "SPARE1") (class "Default")
      (node (ref "J6") (pin "10") (pinfunction "10_10") (pintype "passive"))
      (node (ref "J6") (pin "9") (pinfunction "9_9") (pintype "passive"))
      (node (ref "JP2") (pin "5") (pinfunction "5_5") (pintype "passive"))
    )
    (net (code "131") (name "SPARE2") (class "Default")
      (node (ref "J6") (pin "7") (pinfunction "7_7") (pintype "passive"))
      (node (ref "J6") (pin "8") (pinfunction "8_8") (pintype "passive"))
      (node (ref "JP2") (pin "4") (pinfunction "4_4") (pintype "passive"))
    )
    (net (code "132") (name "SPARE3") (class "Default")
      (node (ref "J6") (pin "5") (pinfunction "5_5") (pintype "passive"))
      (node (ref "J6") (pin "6") (pinfunction "6_6") (pintype "passive"))
      (node (ref "JP2") (pin "3") (pinfunction "3_3") (pintype "passive"))
    )
    (net (code "133") (name "SPARE4") (class "Default")
      (node (ref "J6") (pin "3") (pinfunction "3_3") (pintype "passive"))
      (node (ref "J6") (pin "4") (pinfunction "4_4") (pintype "passive"))
      (node (ref "JP2") (pin "2") (pinfunction "2_2") (pintype "passive"))
    )
    (net (code "134") (name "SPARE5") (class "Default")
      (node (ref "J6") (pin "1") (pinfunction "1_1") (pintype "passive"))
      (node (ref "J6") (pin "2") (pinfunction "2_2") (pintype "passive"))
      (node (ref "JP2") (pin "1") (pinfunction "1_1") (pintype "passive"))
    )
    (net (code "135") (name "SPI1_MISO") (class "Default")
      (node (ref "J15") (pin "6") (pinfunction "6_6") (pintype "passive"))
      (node (ref "J19") (pin "6") (pinfunction "6_6") (pintype "passive"))
      (node (ref "TP22") (pin "1") (pinfunction "1_1") (pintype "passive"))
      (node (ref "U7") (pin "22") (pinfunction "PA6_22") (pintype "bidirectional"))
    )
    (net (code "136") (name "SPI1_MOSI") (class "Default")
      (node (ref "J15") (pin "8") (pinfunction "8_8") (pintype "passive"))
      (node (ref "J19") (pin "8") (pinfunction "8_8") (pintype "passive"))
      (node (ref "TP18") (pin "1") (pinfunction "1_1") (pintype "passive"))
      (node (ref "U7") (pin "23") (pinfunction "PA7_23") (pintype "bidirectional"))
    )
    (net (code "137") (name "SPI1_SCK") (class "Default")
      (node (ref "J15") (pin "4") (pinfunction "4_4") (pintype "passive"))
      (node (ref "J19") (pin "4") (pinfunction "4_4") (pintype "passive"))
      (node (ref "TP23") (pin "1") (pinfunction "1_1") (pintype "passive"))
      (node (ref "U7") (pin "21") (pinfunction "PA5_21") (pintype "bidirectional"))
    )
    (net (code "138") (name "SPI2_MISO") (class "Default")
      (node (ref "JP11") (pin "5") (pinfunction "5_5") (pintype "passive"))
      (node (ref "U7") (pin "35") (pinfunction "PB14_35") (pintype "bidirectional"))
    )
    (net (code "139") (name "SPI2_MOSI") (class "Default")
      (node (ref "JP11") (pin "7") (pinfunction "7_7") (pintype "passive"))
      (node (ref "U7") (pin "36") (pinfunction "PB15_36") (pintype "bidirectional"))
    )
    (net (code "140") (name "SPI2_SCK") (class "Default")
      (node (ref "JP11") (pin "3") (pinfunction "3_3") (pintype "passive"))
      (node (ref "U7") (pin "34") (pinfunction "PB13_34") (pintype "bidirectional"))
    )
    (net (code "141") (name "SWCLK") (class "Default")
      (node (ref "J7") (pin "4") (pinfunction "SWDCLK/TCK_4") (pintype "passive"))
      (node (ref "U7") (pin "49") (pinfunction "PA14_49") (pintype "bidirectional"))
    )
    (net (code "142") (name "SWDIO") (class "Default")
      (node (ref "J7") (pin "2") (pinfunction "SWDIO/TMS_2") (pintype "passive"))
      (node (ref "U7") (pin "46") (pinfunction "PA13_46") (pintype "bidirectional"))
    )
    (net (code "143") (name "SYSCLK1") (class "Default")
      (node (ref "J8") (pin "FEED") (pinfunction "SIGNAL_FEED") (pintype "bidirectional"))
      (node (ref "U11") (pin "13") (pinfunction "SYSCLK_13") (pintype "bidirectional"))
    )
    (net (code "144") (name "USART2_RX") (class "Default")
      (node (ref "U$2") (pin "P$3") (pinfunction "TXO_P$3") (pintype "passive"))
      (node (ref "U7") (pin "17") (pinfunction "PA3_17") (pintype "bidirectional"))
    )
    (net (code "145") (name "USART2_TX") (class "Default")
      (node (ref "U$2") (pin "P$2") (pinfunction "RXI_P$2") (pintype "passive"))
      (node (ref "U7") (pin "16") (pinfunction "PA2_16") (pintype "bidirectional"))
    )
    (net (code "146") (name "VBUS") (class "Default")
      (node (ref "C1") (pin "1") (pinfunction "1_1") (pintype "passive"))
      (node (ref "J6") (pin "21") (pinfunction "21_21") (pintype "passive"))
      (node (ref "J6") (pin "22") (pinfunction "22_22") (pintype "passive"))
      (node (ref "J6") (pin "23") (pinfunction "23_23") (pintype "passive"))
      (node (ref "J6") (pin "24") (pinfunction "24_24") (pintype "passive"))
      (node (ref "J6") (pin "25") (pinfunction "25_25") (pintype "passive"))
      (node (ref "J6") (pin "26") (pinfunction "26_26") (pintype "passive"))
      (node (ref "JP10") (pin "1") (pinfunction "1_1") (pintype "passive"))
      (node (ref "JP10") (pin "2") (pinfunction "2_2") (pintype "passive"))
      (node (ref "JP10") (pin "3") (pinfunction "3_3") (pintype "passive"))
      (node (ref "JP10") (pin "4") (pinfunction "4_4") (pintype "passive"))
      (node (ref "R5") (pin "2") (pinfunction "2_2") (pintype "passive"))
      (node (ref "U4") (pin "4") (pinfunction "VIN_4") (pintype "power_in"))
    )
    (net (code "147") (name "VBUSP") (class "Default")
      (node (ref "C10") (pin "1") (pinfunction "1_1") (pintype "passive"))
      (node (ref "C7") (pin "1") (pinfunction "1_1") (pintype "passive"))
      (node (ref "JP4") (pin "1") (pinfunction "1_1") (pintype "passive"))
      (node (ref "JP4") (pin "2") (pinfunction "2_2") (pintype "passive"))
      (node (ref "JP8") (pin "1") (pinfunction "1_1") (pintype "passive"))
      (node (ref "R1") (pin "2") (pinfunction "2_2") (pintype "passive"))
      (node (ref "R7") (pin "2") (pinfunction "2_2") (pintype "passive"))
      (node (ref "TP20") (pin "1") (pinfunction "1_1") (pintype "passive"))
      (node (ref "U4") (pin "5") (pinfunction "VOUT_5") (pintype "power_in"))
      (node (ref "U5") (pin "2") (pinfunction "VIN_2") (pintype "power_in"))
      (node (ref "U5") (pin "3") (pinfunction "VIN_3") (pintype "power_in"))
      (node (ref "U5") (pin "4") (pinfunction "EN_4") (pintype "input"))
      (node (ref "U5") (pin "8") (pinfunction "VIN_8") (pintype "power_in"))
    )
    (net (code "148") (name "VCAP") (class "Default")
      (node (ref "C14") (pin "1") (pinfunction "1_1") (pintype "passive"))
      (node (ref "U7") (pin "30") (pinfunction "VCAP_1_30") (pintype "bidirectional"))
    )
    (net (code "149") (name "VDDI") (class "Default")
      (node (ref "C19") (pin "1") (pinfunction "1_1") (pintype "passive"))
      (node (ref "C21") (pin "1") (pinfunction "1_1") (pintype "passive"))
      (node (ref "U9") (pin "C1") (pinfunction "VDDI_C1") (pintype "power_in"))
      (node (ref "U9") (pin "C2") (pinfunction "VDDI_C2") (pintype "power_in"))
    )
    (net (code "150") (name "WDT") (class "Default")
      (node (ref "R3") (pin "2") (pinfunction "2_2") (pintype "passive"))
      (node (ref "TP3") (pin "1") (pinfunction "1_1") (pintype "passive"))
      (node (ref "U6") (pin "1") (pinfunction "WDI_1") (pintype "input"))
      (node (ref "U7") (pin "14") (pinfunction "PA0_14") (pintype "bidirectional"))
    )
    (net (code "151") (name "unconnected-(J7-NC{slash}TDI-Pad8)") (class "Default")
      (node (ref "J7") (pin "8") (pinfunction "NC/TDI_8") (pintype "passive"))
    )
    (net (code "152") (name "unconnected-(J7-SWO{slash}TDO-Pad6)") (class "Default")
      (node (ref "J7") (pin "6") (pinfunction "SWO/TDO_6") (pintype "passive"))
    )
    (net (code "153") (name "unconnected-(JP2-Pad6)") (class "Default")
      (node (ref "JP2") (pin "6") (pinfunction "6_6") (pintype "passive"))
    )
    (net (code "154") (name "unconnected-(R15-44-Pad4)") (class "Default")
      (node (ref "R15") (pin "4") (pinfunction "44_4") (pintype "passive"))
    )
    (net (code "155") (name "unconnected-(R15-66-Pad6)") (class "Default")
      (node (ref "R15") (pin "6") (pinfunction "66_6") (pintype "passive"))
    )
    (net (code "156") (name "unconnected-(R15-77-Pad7)") (class "Default")
      (node (ref "R15") (pin "7") (pinfunction "77_7") (pintype "passive"))
    )
    (net (code "157") (name "unconnected-(R15-88-Pad8)") (class "Default")
      (node (ref "R15") (pin "8") (pinfunction "88_8") (pintype "passive"))
    )
    (net (code "158") (name "unconnected-(U$2-CTS-PadP$5)") (class "Default")
      (node (ref "U$2") (pin "P$5") (pinfunction "CTS_P$5") (pintype "passive"))
    )
    (net (code "159") (name "unconnected-(U$2-DTR-PadP$1)") (class "Default")
      (node (ref "U$2") (pin "P$1") (pinfunction "DTR_P$1") (pintype "passive"))
    )
    (net (code "160") (name "unconnected-(U4-DV{slash}DT-Pad2)") (class "Default")
      (node (ref "U4") (pin "2") (pinfunction "DV/DT_2") (pintype "bidirectional"))
    )
    (net (code "161") (name "unconnected-(U4-OVLO-Pad8)") (class "Default")
      (node (ref "U4") (pin "8") (pinfunction "OVLO_8") (pintype "bidirectional"))
    )
    (net (code "162") (name "unconnected-(U6-NC-Pad3)") (class "Default")
      (node (ref "U6") (pin "3") (pinfunction "NC_3") (pintype "no_connect"))
    )
    (net (code "163") (name "unconnected-(U11-ANTSEL-Pad21)") (class "Default")
      (node (ref "U11") (pin "21") (pinfunction "ANTSEL_21") (pintype "bidirectional"))
    )
    (net (code "164") (name "unconnected-(U11-DATA-Pad11)") (class "Default")
      (node (ref "U11") (pin "11") (pinfunction "DATA_11") (pintype "bidirectional"))
    )
    (net (code "165") (name "unconnected-(U11-DCLK-Pad12)") (class "Default")
      (node (ref "U11") (pin "12") (pinfunction "DCLK_12") (pintype "bidirectional"))
    )
    (net (code "166") (name "unconnected-(U11-FILT-Pad8)") (class "Default")
      (node (ref "U11") (pin "8") (pinfunction "FILT_8") (pintype "output"))
    )
    (net (code "167") (name "unconnected-(U13-ANTSEL-Pad21)") (class "Default")
      (node (ref "U13") (pin "21") (pinfunction "ANTSEL_21") (pintype "bidirectional"))
    )
    (net (code "168") (name "unconnected-(U13-DATA-Pad11)") (class "Default")
      (node (ref "U13") (pin "11") (pinfunction "DATA_11") (pintype "bidirectional"))
    )
    (net (code "169") (name "unconnected-(U13-DCLK-Pad12)") (class "Default")
      (node (ref "U13") (pin "12") (pinfunction "DCLK_12") (pintype "bidirectional"))
    )
    (net (code "170") (name "unconnected-(U13-FILT-Pad8)") (class "Default")
      (node (ref "U13") (pin "8") (pinfunction "FILT_8") (pintype "output"))
    )
    (net (code "171") (name "unconnected-(X3-VCTRL-Pad1)") (class "Default")
      (node (ref "X3") (pin "1") (pinfunction "VCTRL_1") (pintype "input"))
    )
    (net (code "172") (name "unconnected-(X4-VCTRL-Pad1)") (class "Default")
      (node (ref "X4") (pin "1") (pinfunction "VCTRL_1") (pintype "input"))
    )
    (net (code "173") (name "~{OPD_ENABLE}") (class "Default")
      (node (ref "D4") (pin "C") (pinfunction "C_C") (pintype "passive"))
      (node (ref "TP13") (pin "1") (pinfunction "1_1") (pintype "passive"))
      (node (ref "U1") (pin "3") (pinfunction "~{ON}_3") (pintype "input"))
      (node (ref "U7") (pin "28") (pinfunction "PB2_28") (pintype "bidirectional"))
    )
    (net (code "174") (name "~{SD}") (class "Default")
      (node (ref "J6") (pin "39") (pinfunction "39_39") (pintype "passive"))
      (node (ref "J6") (pin "40") (pinfunction "40_40") (pintype "passive"))
      (node (ref "JP10") (pin "10") (pinfunction "10_10") (pintype "passive"))
      (node (ref "JP10") (pin "9") (pinfunction "9_9") (pintype "passive"))
      (node (ref "R13") (pin "2") (pinfunction "2_2") (pintype "passive"))
      (node (ref "U6") (pin "7") (pinfunction "~{WDO}_7") (pintype "output"))
    )
  )
)
